# gmatrix.net
KiCad netlist of a schematic drawn in EAGLE
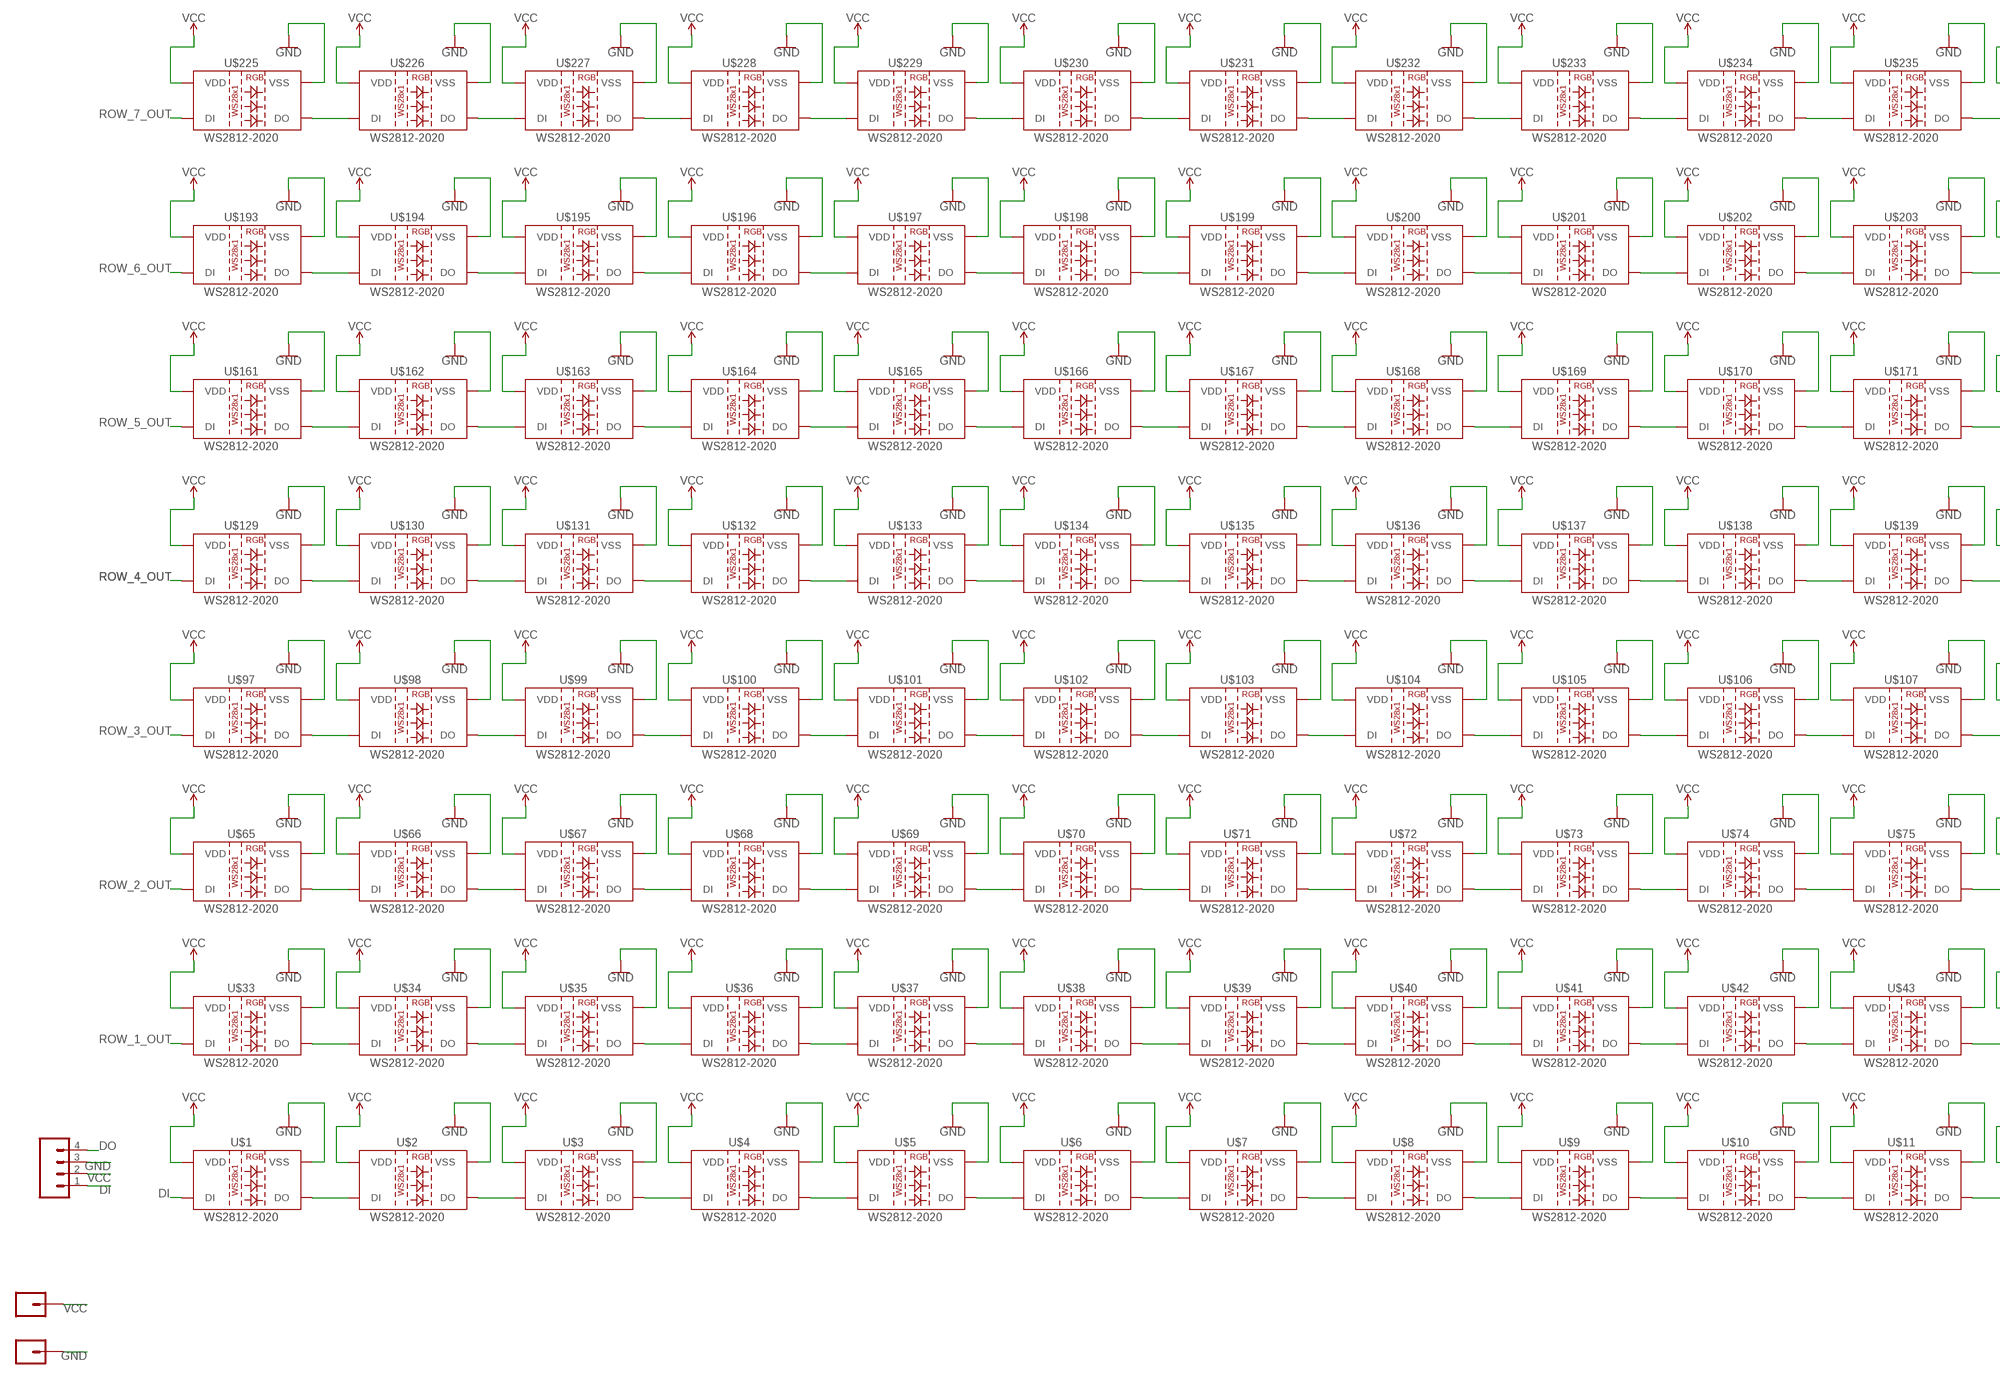
[diagram p0: schematic, sheet 1, part 1 of 3]
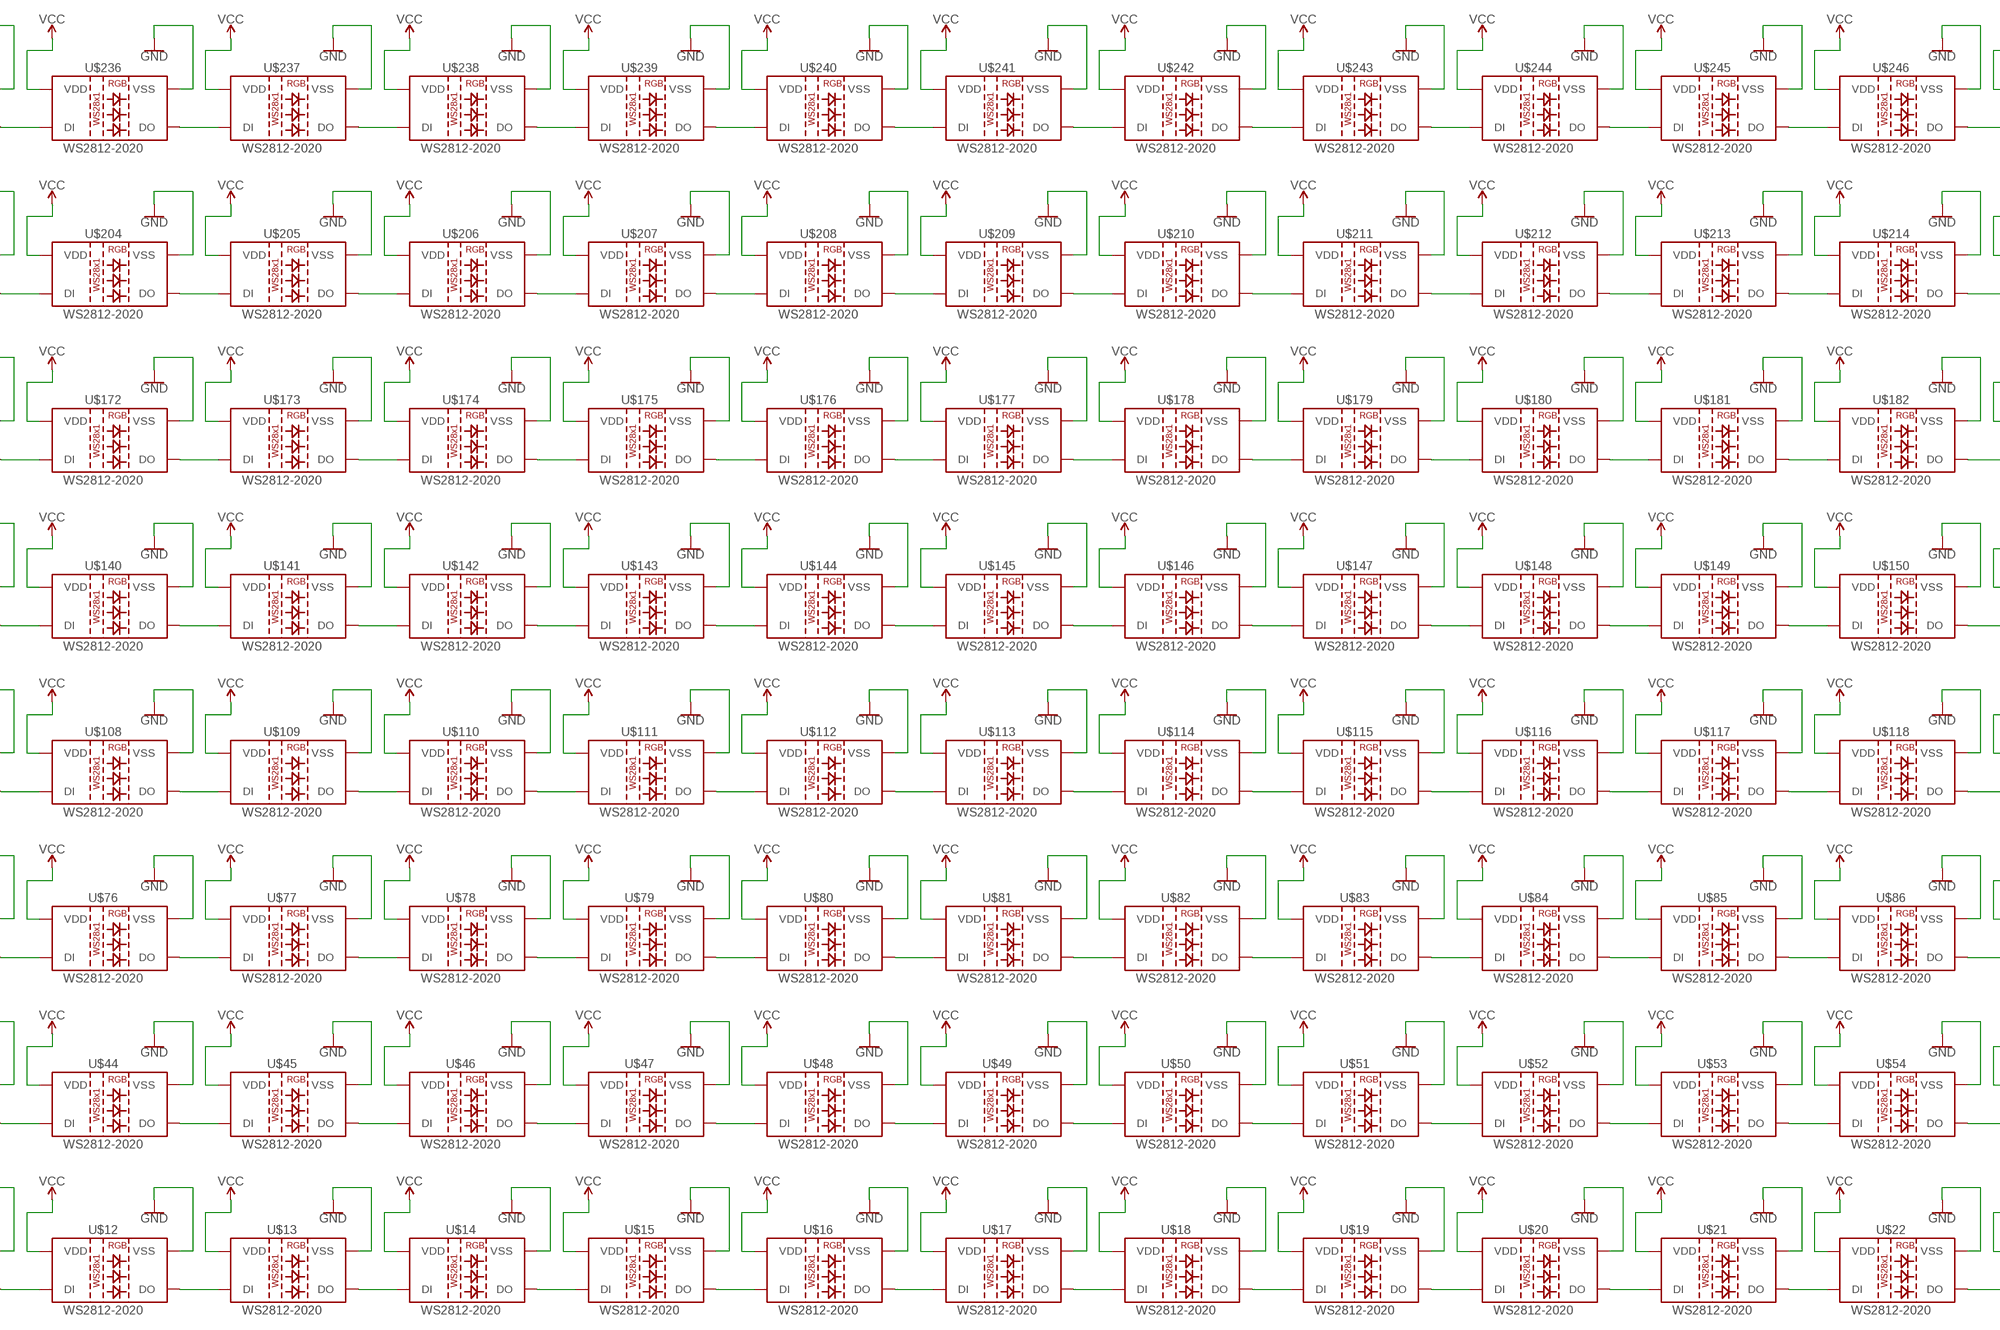
[diagram p1: schematic, sheet 1, part 2 of 3]
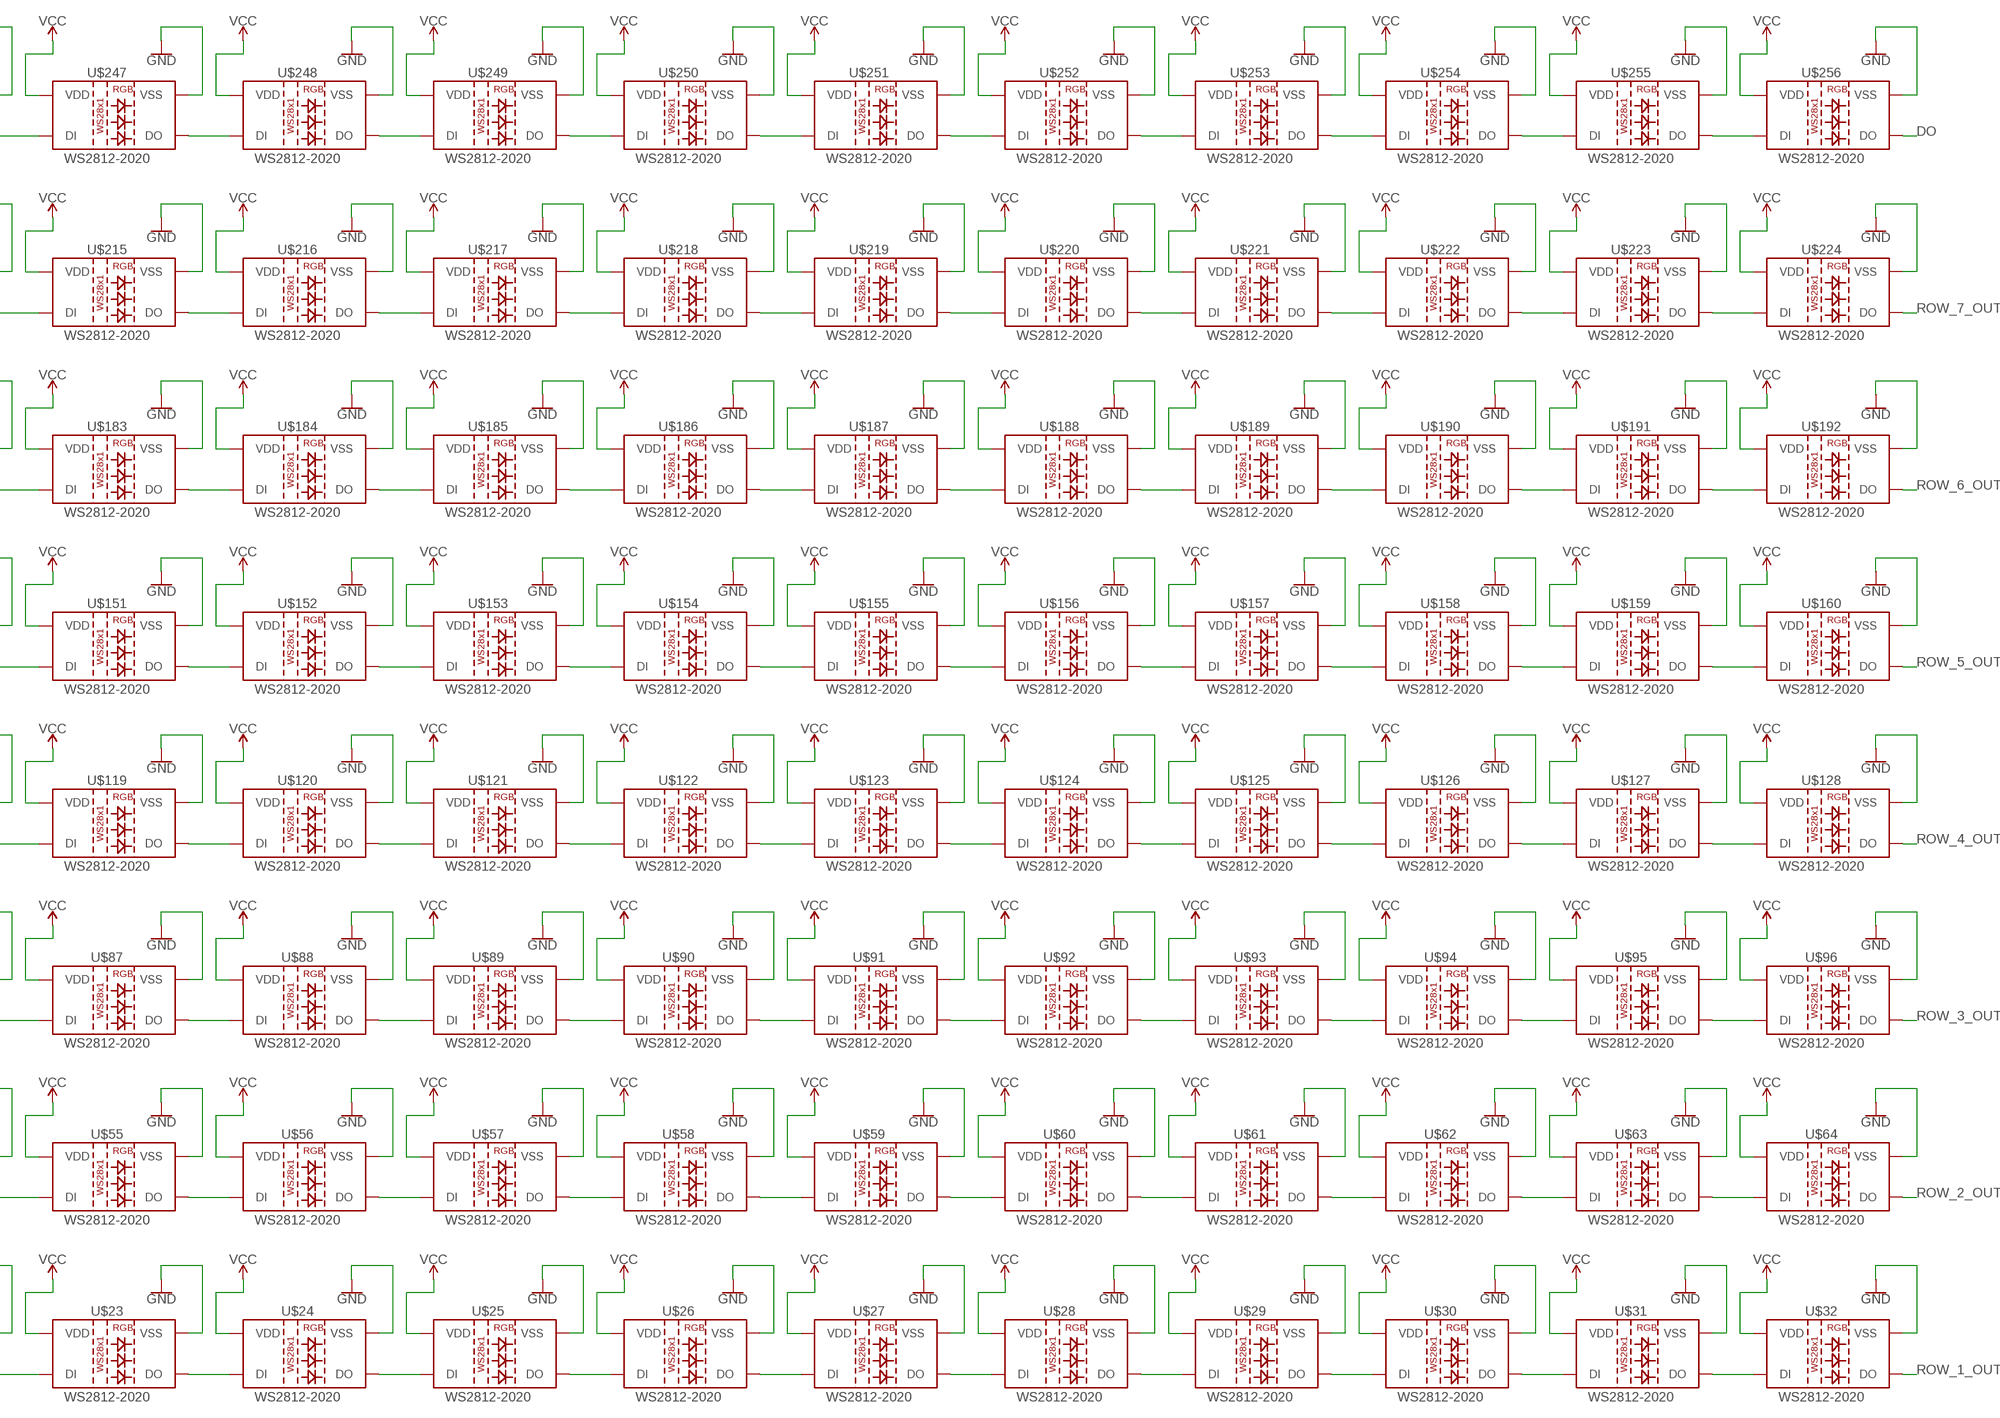
[diagram p2: schematic, sheet 1, part 3 of 3]

(export (version "E")
  (design (tool "Eeschema 10.0.6"))
  (components
    (comp (ref "J1")
      (value "CONN_041X04_NO_SILK")
      (footprint "eagle-import:1X04_NO_SILK")
      (libsource (lib "eagle-import") (part "CONN_041X04_NO_SILK"))
    )
    (comp (ref "J2")
      (value "CONN_01PTH_NO_SILK_KIT")
      (footprint "eagle-import:1X01NS_KIT")
      (libsource (lib "eagle-import") (part "CONN_01PTH_NO_SILK_KIT"))
    )
    (comp (ref "J3")
      (value "CONN_01PTH_NO_SILK_KIT")
      (footprint "eagle-import:1X01NS_KIT")
      (libsource (lib "eagle-import") (part "CONN_01PTH_NO_SILK_KIT"))
    )
    (comp (ref "U$1")
      (value "WS2812-2020")
      (footprint "eagle-import:WS2812-2020")
      (libsource (lib "eagle-import") (part "WS2812-2020"))
    )
    (comp (ref "U$2")
      (value "WS2812-2020")
      (footprint "eagle-import:WS2812-2020")
      (libsource (lib "eagle-import") (part "WS2812-2020"))
    )
    (comp (ref "U$3")
      (value "WS2812-2020")
      (footprint "eagle-import:WS2812-2020")
      (libsource (lib "eagle-import") (part "WS2812-2020"))
    )
    (comp (ref "U$4")
      (value "WS2812-2020")
      (footprint "eagle-import:WS2812-2020")
      (libsource (lib "eagle-import") (part "WS2812-2020"))
    )
    (comp (ref "U$5")
      (value "WS2812-2020")
      (footprint "eagle-import:WS2812-2020")
      (libsource (lib "eagle-import") (part "WS2812-2020"))
    )
    (comp (ref "U$6")
      (value "WS2812-2020")
      (footprint "eagle-import:WS2812-2020")
      (libsource (lib "eagle-import") (part "WS2812-2020"))
    )
    (comp (ref "U$7")
      (value "WS2812-2020")
      (footprint "eagle-import:WS2812-2020")
      (libsource (lib "eagle-import") (part "WS2812-2020"))
    )
    (comp (ref "U$8")
      (value "WS2812-2020")
      (footprint "eagle-import:WS2812-2020")
      (libsource (lib "eagle-import") (part "WS2812-2020"))
    )
    (comp (ref "U$9")
      (value "WS2812-2020")
      (footprint "eagle-import:WS2812-2020")
      (libsource (lib "eagle-import") (part "WS2812-2020"))
    )
    (comp (ref "U$10")
      (value "WS2812-2020")
      (footprint "eagle-import:WS2812-2020")
      (libsource (lib "eagle-import") (part "WS2812-2020"))
    )
    (comp (ref "U$11")
      (value "WS2812-2020")
      (footprint "eagle-import:WS2812-2020")
      (libsource (lib "eagle-import") (part "WS2812-2020"))
    )
    (comp (ref "U$12")
      (value "WS2812-2020")
      (footprint "eagle-import:WS2812-2020")
      (libsource (lib "eagle-import") (part "WS2812-2020"))
    )
    (comp (ref "U$13")
      (value "WS2812-2020")
      (footprint "eagle-import:WS2812-2020")
      (libsource (lib "eagle-import") (part "WS2812-2020"))
    )
    (comp (ref "U$14")
      (value "WS2812-2020")
      (footprint "eagle-import:WS2812-2020")
      (libsource (lib "eagle-import") (part "WS2812-2020"))
    )
    (comp (ref "U$15")
      (value "WS2812-2020")
      (footprint "eagle-import:WS2812-2020")
      (libsource (lib "eagle-import") (part "WS2812-2020"))
    )
    (comp (ref "U$16")
      (value "WS2812-2020")
      (footprint "eagle-import:WS2812-2020")
      (libsource (lib "eagle-import") (part "WS2812-2020"))
    )
    (comp (ref "U$17")
      (value "WS2812-2020")
      (footprint "eagle-import:WS2812-2020")
      (libsource (lib "eagle-import") (part "WS2812-2020"))
    )
    (comp (ref "U$18")
      (value "WS2812-2020")
      (footprint "eagle-import:WS2812-2020")
      (libsource (lib "eagle-import") (part "WS2812-2020"))
    )
    (comp (ref "U$19")
      (value "WS2812-2020")
      (footprint "eagle-import:WS2812-2020")
      (libsource (lib "eagle-import") (part "WS2812-2020"))
    )
    (comp (ref "U$20")
      (value "WS2812-2020")
      (footprint "eagle-import:WS2812-2020")
      (libsource (lib "eagle-import") (part "WS2812-2020"))
    )
    (comp (ref "U$21")
      (value "WS2812-2020")
      (footprint "eagle-import:WS2812-2020")
      (libsource (lib "eagle-import") (part "WS2812-2020"))
    )
    (comp (ref "U$22")
      (value "WS2812-2020")
      (footprint "eagle-import:WS2812-2020")
      (libsource (lib "eagle-import") (part "WS2812-2020"))
    )
    (comp (ref "U$23")
      (value "WS2812-2020")
      (footprint "eagle-import:WS2812-2020")
      (libsource (lib "eagle-import") (part "WS2812-2020"))
    )
    (comp (ref "U$24")
      (value "WS2812-2020")
      (footprint "eagle-import:WS2812-2020")
      (libsource (lib "eagle-import") (part "WS2812-2020"))
    )
    (comp (ref "U$25")
      (value "WS2812-2020")
      (footprint "eagle-import:WS2812-2020")
      (libsource (lib "eagle-import") (part "WS2812-2020"))
    )
    (comp (ref "U$26")
      (value "WS2812-2020")
      (footprint "eagle-import:WS2812-2020")
      (libsource (lib "eagle-import") (part "WS2812-2020"))
    )
    (comp (ref "U$27")
      (value "WS2812-2020")
      (footprint "eagle-import:WS2812-2020")
      (libsource (lib "eagle-import") (part "WS2812-2020"))
    )
    (comp (ref "U$28")
      (value "WS2812-2020")
      (footprint "eagle-import:WS2812-2020")
      (libsource (lib "eagle-import") (part "WS2812-2020"))
    )
    (comp (ref "U$29")
      (value "WS2812-2020")
      (footprint "eagle-import:WS2812-2020")
      (libsource (lib "eagle-import") (part "WS2812-2020"))
    )
    (comp (ref "U$30")
      (value "WS2812-2020")
      (footprint "eagle-import:WS2812-2020")
      (libsource (lib "eagle-import") (part "WS2812-2020"))
    )
    (comp (ref "U$31")
      (value "WS2812-2020")
      (footprint "eagle-import:WS2812-2020")
      (libsource (lib "eagle-import") (part "WS2812-2020"))
    )
    (comp (ref "U$32")
      (value "WS2812-2020")
      (footprint "eagle-import:WS2812-2020")
      (libsource (lib "eagle-import") (part "WS2812-2020"))
    )
    (comp (ref "U$33")
      (value "WS2812-2020")
      (footprint "eagle-import:WS2812-2020")
      (libsource (lib "eagle-import") (part "WS2812-2020"))
    )
    (comp (ref "U$34")
      (value "WS2812-2020")
      (footprint "eagle-import:WS2812-2020")
      (libsource (lib "eagle-import") (part "WS2812-2020"))
    )
    (comp (ref "U$35")
      (value "WS2812-2020")
      (footprint "eagle-import:WS2812-2020")
      (libsource (lib "eagle-import") (part "WS2812-2020"))
    )
    (comp (ref "U$36")
      (value "WS2812-2020")
      (footprint "eagle-import:WS2812-2020")
      (libsource (lib "eagle-import") (part "WS2812-2020"))
    )
    (comp (ref "U$37")
      (value "WS2812-2020")
      (footprint "eagle-import:WS2812-2020")
      (libsource (lib "eagle-import") (part "WS2812-2020"))
    )
    (comp (ref "U$38")
      (value "WS2812-2020")
      (footprint "eagle-import:WS2812-2020")
      (libsource (lib "eagle-import") (part "WS2812-2020"))
    )
    (comp (ref "U$39")
      (value "WS2812-2020")
      (footprint "eagle-import:WS2812-2020")
      (libsource (lib "eagle-import") (part "WS2812-2020"))
    )
    (comp (ref "U$40")
      (value "WS2812-2020")
      (footprint "eagle-import:WS2812-2020")
      (libsource (lib "eagle-import") (part "WS2812-2020"))
    )
    (comp (ref "U$41")
      (value "WS2812-2020")
      (footprint "eagle-import:WS2812-2020")
      (libsource (lib "eagle-import") (part "WS2812-2020"))
    )
    (comp (ref "U$42")
      (value "WS2812-2020")
      (footprint "eagle-import:WS2812-2020")
      (libsource (lib "eagle-import") (part "WS2812-2020"))
    )
    (comp (ref "U$43")
      (value "WS2812-2020")
      (footprint "eagle-import:WS2812-2020")
      (libsource (lib "eagle-import") (part "WS2812-2020"))
    )
    (comp (ref "U$44")
      (value "WS2812-2020")
      (footprint "eagle-import:WS2812-2020")
      (libsource (lib "eagle-import") (part "WS2812-2020"))
    )
    (comp (ref "U$45")
      (value "WS2812-2020")
      (footprint "eagle-import:WS2812-2020")
      (libsource (lib "eagle-import") (part "WS2812-2020"))
    )
    (comp (ref "U$46")
      (value "WS2812-2020")
      (footprint "eagle-import:WS2812-2020")
      (libsource (lib "eagle-import") (part "WS2812-2020"))
    )
    (comp (ref "U$47")
      (value "WS2812-2020")
      (footprint "eagle-import:WS2812-2020")
      (libsource (lib "eagle-import") (part "WS2812-2020"))
    )
    (comp (ref "U$48")
      (value "WS2812-2020")
      (footprint "eagle-import:WS2812-2020")
      (libsource (lib "eagle-import") (part "WS2812-2020"))
    )
    (comp (ref "U$49")
      (value "WS2812-2020")
      (footprint "eagle-import:WS2812-2020")
      (libsource (lib "eagle-import") (part "WS2812-2020"))
    )
    (comp (ref "U$50")
      (value "WS2812-2020")
      (footprint "eagle-import:WS2812-2020")
      (libsource (lib "eagle-import") (part "WS2812-2020"))
    )
    (comp (ref "U$51")
      (value "WS2812-2020")
      (footprint "eagle-import:WS2812-2020")
      (libsource (lib "eagle-import") (part "WS2812-2020"))
    )
    (comp (ref "U$52")
      (value "WS2812-2020")
      (footprint "eagle-import:WS2812-2020")
      (libsource (lib "eagle-import") (part "WS2812-2020"))
    )
    (comp (ref "U$53")
      (value "WS2812-2020")
      (footprint "eagle-import:WS2812-2020")
      (libsource (lib "eagle-import") (part "WS2812-2020"))
    )
    (comp (ref "U$54")
      (value "WS2812-2020")
      (footprint "eagle-import:WS2812-2020")
      (libsource (lib "eagle-import") (part "WS2812-2020"))
    )
    (comp (ref "U$55")
      (value "WS2812-2020")
      (footprint "eagle-import:WS2812-2020")
      (libsource (lib "eagle-import") (part "WS2812-2020"))
    )
    (comp (ref "U$56")
      (value "WS2812-2020")
      (footprint "eagle-import:WS2812-2020")
      (libsource (lib "eagle-import") (part "WS2812-2020"))
    )
    (comp (ref "U$57")
      (value "WS2812-2020")
      (footprint "eagle-import:WS2812-2020")
      (libsource (lib "eagle-import") (part "WS2812-2020"))
    )
    (comp (ref "U$58")
      (value "WS2812-2020")
      (footprint "eagle-import:WS2812-2020")
      (libsource (lib "eagle-import") (part "WS2812-2020"))
    )
    (comp (ref "U$59")
      (value "WS2812-2020")
      (footprint "eagle-import:WS2812-2020")
      (libsource (lib "eagle-import") (part "WS2812-2020"))
    )
    (comp (ref "U$60")
      (value "WS2812-2020")
      (footprint "eagle-import:WS2812-2020")
      (libsource (lib "eagle-import") (part "WS2812-2020"))
    )
    (comp (ref "U$61")
      (value "WS2812-2020")
      (footprint "eagle-import:WS2812-2020")
      (libsource (lib "eagle-import") (part "WS2812-2020"))
    )
    (comp (ref "U$62")
      (value "WS2812-2020")
      (footprint "eagle-import:WS2812-2020")
      (libsource (lib "eagle-import") (part "WS2812-2020"))
    )
    (comp (ref "U$63")
      (value "WS2812-2020")
      (footprint "eagle-import:WS2812-2020")
      (libsource (lib "eagle-import") (part "WS2812-2020"))
    )
    (comp (ref "U$64")
      (value "WS2812-2020")
      (footprint "eagle-import:WS2812-2020")
      (libsource (lib "eagle-import") (part "WS2812-2020"))
    )
    (comp (ref "U$65")
      (value "WS2812-2020")
      (footprint "eagle-import:WS2812-2020")
      (libsource (lib "eagle-import") (part "WS2812-2020"))
    )
    (comp (ref "U$66")
      (value "WS2812-2020")
      (footprint "eagle-import:WS2812-2020")
      (libsource (lib "eagle-import") (part "WS2812-2020"))
    )
    (comp (ref "U$67")
      (value "WS2812-2020")
      (footprint "eagle-import:WS2812-2020")
      (libsource (lib "eagle-import") (part "WS2812-2020"))
    )
    (comp (ref "U$68")
      (value "WS2812-2020")
      (footprint "eagle-import:WS2812-2020")
      (libsource (lib "eagle-import") (part "WS2812-2020"))
    )
    (comp (ref "U$69")
      (value "WS2812-2020")
      (footprint "eagle-import:WS2812-2020")
      (libsource (lib "eagle-import") (part "WS2812-2020"))
    )
    (comp (ref "U$70")
      (value "WS2812-2020")
      (footprint "eagle-import:WS2812-2020")
      (libsource (lib "eagle-import") (part "WS2812-2020"))
    )
    (comp (ref "U$71")
      (value "WS2812-2020")
      (footprint "eagle-import:WS2812-2020")
      (libsource (lib "eagle-import") (part "WS2812-2020"))
    )
    (comp (ref "U$72")
      (value "WS2812-2020")
      (footprint "eagle-import:WS2812-2020")
      (libsource (lib "eagle-import") (part "WS2812-2020"))
    )
    (comp (ref "U$73")
      (value "WS2812-2020")
      (footprint "eagle-import:WS2812-2020")
      (libsource (lib "eagle-import") (part "WS2812-2020"))
    )
    (comp (ref "U$74")
      (value "WS2812-2020")
      (footprint "eagle-import:WS2812-2020")
      (libsource (lib "eagle-import") (part "WS2812-2020"))
    )
    (comp (ref "U$75")
      (value "WS2812-2020")
      (footprint "eagle-import:WS2812-2020")
      (libsource (lib "eagle-import") (part "WS2812-2020"))
    )
    (comp (ref "U$76")
      (value "WS2812-2020")
      (footprint "eagle-import:WS2812-2020")
      (libsource (lib "eagle-import") (part "WS2812-2020"))
    )
    (comp (ref "U$77")
      (value "WS2812-2020")
      (footprint "eagle-import:WS2812-2020")
      (libsource (lib "eagle-import") (part "WS2812-2020"))
    )
    (comp (ref "U$78")
      (value "WS2812-2020")
      (footprint "eagle-import:WS2812-2020")
      (libsource (lib "eagle-import") (part "WS2812-2020"))
    )
    (comp (ref "U$79")
      (value "WS2812-2020")
      (footprint "eagle-import:WS2812-2020")
      (libsource (lib "eagle-import") (part "WS2812-2020"))
    )
    (comp (ref "U$80")
      (value "WS2812-2020")
      (footprint "eagle-import:WS2812-2020")
      (libsource (lib "eagle-import") (part "WS2812-2020"))
    )
    (comp (ref "U$81")
      (value "WS2812-2020")
      (footprint "eagle-import:WS2812-2020")
      (libsource (lib "eagle-import") (part "WS2812-2020"))
    )
    (comp (ref "U$82")
      (value "WS2812-2020")
      (footprint "eagle-import:WS2812-2020")
      (libsource (lib "eagle-import") (part "WS2812-2020"))
    )
    (comp (ref "U$83")
      (value "WS2812-2020")
      (footprint "eagle-import:WS2812-2020")
      (libsource (lib "eagle-import") (part "WS2812-2020"))
    )
    (comp (ref "U$84")
      (value "WS2812-2020")
      (footprint "eagle-import:WS2812-2020")
      (libsource (lib "eagle-import") (part "WS2812-2020"))
    )
    (comp (ref "U$85")
      (value "WS2812-2020")
      (footprint "eagle-import:WS2812-2020")
      (libsource (lib "eagle-import") (part "WS2812-2020"))
    )
    (comp (ref "U$86")
      (value "WS2812-2020")
      (footprint "eagle-import:WS2812-2020")
      (libsource (lib "eagle-import") (part "WS2812-2020"))
    )
    (comp (ref "U$87")
      (value "WS2812-2020")
      (footprint "eagle-import:WS2812-2020")
      (libsource (lib "eagle-import") (part "WS2812-2020"))
    )
    (comp (ref "U$88")
      (value "WS2812-2020")
      (footprint "eagle-import:WS2812-2020")
      (libsource (lib "eagle-import") (part "WS2812-2020"))
    )
    (comp (ref "U$89")
      (value "WS2812-2020")
      (footprint "eagle-import:WS2812-2020")
      (libsource (lib "eagle-import") (part "WS2812-2020"))
    )
    (comp (ref "U$90")
      (value "WS2812-2020")
      (footprint "eagle-import:WS2812-2020")
      (libsource (lib "eagle-import") (part "WS2812-2020"))
    )
    (comp (ref "U$91")
      (value "WS2812-2020")
      (footprint "eagle-import:WS2812-2020")
      (libsource (lib "eagle-import") (part "WS2812-2020"))
    )
    (comp (ref "U$92")
      (value "WS2812-2020")
      (footprint "eagle-import:WS2812-2020")
      (libsource (lib "eagle-import") (part "WS2812-2020"))
    )
    (comp (ref "U$93")
      (value "WS2812-2020")
      (footprint "eagle-import:WS2812-2020")
      (libsource (lib "eagle-import") (part "WS2812-2020"))
    )
    (comp (ref "U$94")
      (value "WS2812-2020")
      (footprint "eagle-import:WS2812-2020")
      (libsource (lib "eagle-import") (part "WS2812-2020"))
    )
    (comp (ref "U$95")
      (value "WS2812-2020")
      (footprint "eagle-import:WS2812-2020")
      (libsource (lib "eagle-import") (part "WS2812-2020"))
    )
    (comp (ref "U$96")
      (value "WS2812-2020")
      (footprint "eagle-import:WS2812-2020")
      (libsource (lib "eagle-import") (part "WS2812-2020"))
    )
    (comp (ref "U$97")
      (value "WS2812-2020")
      (footprint "eagle-import:WS2812-2020")
      (libsource (lib "eagle-import") (part "WS2812-2020"))
    )
    (comp (ref "U$98")
      (value "WS2812-2020")
      (footprint "eagle-import:WS2812-2020")
      (libsource (lib "eagle-import") (part "WS2812-2020"))
    )
    (comp (ref "U$99")
      (value "WS2812-2020")
      (footprint "eagle-import:WS2812-2020")
      (libsource (lib "eagle-import") (part "WS2812-2020"))
    )
    (comp (ref "U$100")
      (value "WS2812-2020")
      (footprint "eagle-import:WS2812-2020")
      (libsource (lib "eagle-import") (part "WS2812-2020"))
    )
    (comp (ref "U$101")
      (value "WS2812-2020")
      (footprint "eagle-import:WS2812-2020")
      (libsource (lib "eagle-import") (part "WS2812-2020"))
    )
    (comp (ref "U$102")
      (value "WS2812-2020")
      (footprint "eagle-import:WS2812-2020")
      (libsource (lib "eagle-import") (part "WS2812-2020"))
    )
    (comp (ref "U$103")
      (value "WS2812-2020")
      (footprint "eagle-import:WS2812-2020")
      (libsource (lib "eagle-import") (part "WS2812-2020"))
    )
    (comp (ref "U$104")
      (value "WS2812-2020")
      (footprint "eagle-import:WS2812-2020")
      (libsource (lib "eagle-import") (part "WS2812-2020"))
    )
    (comp (ref "U$105")
      (value "WS2812-2020")
      (footprint "eagle-import:WS2812-2020")
      (libsource (lib "eagle-import") (part "WS2812-2020"))
    )
    (comp (ref "U$106")
      (value "WS2812-2020")
      (footprint "eagle-import:WS2812-2020")
      (libsource (lib "eagle-import") (part "WS2812-2020"))
    )
    (comp (ref "U$107")
      (value "WS2812-2020")
      (footprint "eagle-import:WS2812-2020")
      (libsource (lib "eagle-import") (part "WS2812-2020"))
    )
    (comp (ref "U$108")
      (value "WS2812-2020")
      (footprint "eagle-import:WS2812-2020")
      (libsource (lib "eagle-import") (part "WS2812-2020"))
    )
    (comp (ref "U$109")
      (value "WS2812-2020")
      (footprint "eagle-import:WS2812-2020")
      (libsource (lib "eagle-import") (part "WS2812-2020"))
    )
    (comp (ref "U$110")
      (value "WS2812-2020")
      (footprint "eagle-import:WS2812-2020")
      (libsource (lib "eagle-import") (part "WS2812-2020"))
    )
    (comp (ref "U$111")
      (value "WS2812-2020")
      (footprint "eagle-import:WS2812-2020")
      (libsource (lib "eagle-import") (part "WS2812-2020"))
    )
    (comp (ref "U$112")
      (value "WS2812-2020")
      (footprint "eagle-import:WS2812-2020")
      (libsource (lib "eagle-import") (part "WS2812-2020"))
    )
    (comp (ref "U$113")
      (value "WS2812-2020")
      (footprint "eagle-import:WS2812-2020")
      (libsource (lib "eagle-import") (part "WS2812-2020"))
    )
    (comp (ref "U$114")
      (value "WS2812-2020")
      (footprint "eagle-import:WS2812-2020")
      (libsource (lib "eagle-import") (part "WS2812-2020"))
    )
    (comp (ref "U$115")
      (value "WS2812-2020")
      (footprint "eagle-import:WS2812-2020")
      (libsource (lib "eagle-import") (part "WS2812-2020"))
    )
    (comp (ref "U$116")
      (value "WS2812-2020")
      (footprint "eagle-import:WS2812-2020")
      (libsource (lib "eagle-import") (part "WS2812-2020"))
    )
    (comp (ref "U$117")
      (value "WS2812-2020")
      (footprint "eagle-import:WS2812-2020")
      (libsource (lib "eagle-import") (part "WS2812-2020"))
    )
    (comp (ref "U$118")
      (value "WS2812-2020")
      (footprint "eagle-import:WS2812-2020")
      (libsource (lib "eagle-import") (part "WS2812-2020"))
    )
    (comp (ref "U$119")
      (value "WS2812-2020")
      (footprint "eagle-import:WS2812-2020")
      (libsource (lib "eagle-import") (part "WS2812-2020"))
    )
    (comp (ref "U$120")
      (value "WS2812-2020")
      (footprint "eagle-import:WS2812-2020")
      (libsource (lib "eagle-import") (part "WS2812-2020"))
    )
    (comp (ref "U$121")
      (value "WS2812-2020")
      (footprint "eagle-import:WS2812-2020")
      (libsource (lib "eagle-import") (part "WS2812-2020"))
    )
    (comp (ref "U$122")
      (value "WS2812-2020")
      (footprint "eagle-import:WS2812-2020")
      (libsource (lib "eagle-import") (part "WS2812-2020"))
    )
    (comp (ref "U$123")
      (value "WS2812-2020")
      (footprint "eagle-import:WS2812-2020")
      (libsource (lib "eagle-import") (part "WS2812-2020"))
    )
    (comp (ref "U$124")
      (value "WS2812-2020")
      (footprint "eagle-import:WS2812-2020")
      (libsource (lib "eagle-import") (part "WS2812-2020"))
    )
    (comp (ref "U$125")
      (value "WS2812-2020")
      (footprint "eagle-import:WS2812-2020")
      (libsource (lib "eagle-import") (part "WS2812-2020"))
    )
    (comp (ref "U$126")
      (value "WS2812-2020")
      (footprint "eagle-import:WS2812-2020")
      (libsource (lib "eagle-import") (part "WS2812-2020"))
    )
    (comp (ref "U$127")
      (value "WS2812-2020")
      (footprint "eagle-import:WS2812-2020")
      (libsource (lib "eagle-import") (part "WS2812-2020"))
    )
    (comp (ref "U$128")
      (value "WS2812-2020")
      (footprint "eagle-import:WS2812-2020")
      (libsource (lib "eagle-import") (part "WS2812-2020"))
    )
    (comp (ref "U$129")
      (value "WS2812-2020")
      (footprint "eagle-import:WS2812-2020")
      (libsource (lib "eagle-import") (part "WS2812-2020"))
    )
    (comp (ref "U$130")
      (value "WS2812-2020")
      (footprint "eagle-import:WS2812-2020")
      (libsource (lib "eagle-import") (part "WS2812-2020"))
    )
    (comp (ref "U$131")
      (value "WS2812-2020")
      (footprint "eagle-import:WS2812-2020")
      (libsource (lib "eagle-import") (part "WS2812-2020"))
    )
    (comp (ref "U$132")
      (value "WS2812-2020")
      (footprint "eagle-import:WS2812-2020")
      (libsource (lib "eagle-import") (part "WS2812-2020"))
    )
    (comp (ref "U$133")
      (value "WS2812-2020")
      (footprint "eagle-import:WS2812-2020")
      (libsource (lib "eagle-import") (part "WS2812-2020"))
    )
    (comp (ref "U$134")
      (value "WS2812-2020")
      (footprint "eagle-import:WS2812-2020")
      (libsource (lib "eagle-import") (part "WS2812-2020"))
    )
    (comp (ref "U$135")
      (value "WS2812-2020")
      (footprint "eagle-import:WS2812-2020")
      (libsource (lib "eagle-import") (part "WS2812-2020"))
    )
    (comp (ref "U$136")
      (value "WS2812-2020")
      (footprint "eagle-import:WS2812-2020")
      (libsource (lib "eagle-import") (part "WS2812-2020"))
    )
    (comp (ref "U$137")
      (value "WS2812-2020")
      (footprint "eagle-import:WS2812-2020")
      (libsource (lib "eagle-import") (part "WS2812-2020"))
    )
    (comp (ref "U$138")
      (value "WS2812-2020")
      (footprint "eagle-import:WS2812-2020")
      (libsource (lib "eagle-import") (part "WS2812-2020"))
    )
    (comp (ref "U$139")
      (value "WS2812-2020")
      (footprint "eagle-import:WS2812-2020")
      (libsource (lib "eagle-import") (part "WS2812-2020"))
    )
    (comp (ref "U$140")
      (value "WS2812-2020")
      (footprint "eagle-import:WS2812-2020")
      (libsource (lib "eagle-import") (part "WS2812-2020"))
    )
    (comp (ref "U$141")
      (value "WS2812-2020")
      (footprint "eagle-import:WS2812-2020")
      (libsource (lib "eagle-import") (part "WS2812-2020"))
    )
    (comp (ref "U$142")
      (value "WS2812-2020")
      (footprint "eagle-import:WS2812-2020")
      (libsource (lib "eagle-import") (part "WS2812-2020"))
    )
    (comp (ref "U$143")
      (value "WS2812-2020")
      (footprint "eagle-import:WS2812-2020")
      (libsource (lib "eagle-import") (part "WS2812-2020"))
    )
    (comp (ref "U$144")
      (value "WS2812-2020")
      (footprint "eagle-import:WS2812-2020")
      (libsource (lib "eagle-import") (part "WS2812-2020"))
    )
    (comp (ref "U$145")
      (value "WS2812-2020")
      (footprint "eagle-import:WS2812-2020")
      (libsource (lib "eagle-import") (part "WS2812-2020"))
    )
    (comp (ref "U$146")
      (value "WS2812-2020")
      (footprint "eagle-import:WS2812-2020")
      (libsource (lib "eagle-import") (part "WS2812-2020"))
    )
    (comp (ref "U$147")
      (value "WS2812-2020")
      (footprint "eagle-import:WS2812-2020")
      (libsource (lib "eagle-import") (part "WS2812-2020"))
    )
    (comp (ref "U$148")
      (value "WS2812-2020")
      (footprint "eagle-import:WS2812-2020")
      (libsource (lib "eagle-import") (part "WS2812-2020"))
    )
    (comp (ref "U$149")
      (value "WS2812-2020")
      (footprint "eagle-import:WS2812-2020")
      (libsource (lib "eagle-import") (part "WS2812-2020"))
    )
    (comp (ref "U$150")
      (value "WS2812-2020")
      (footprint "eagle-import:WS2812-2020")
      (libsource (lib "eagle-import") (part "WS2812-2020"))
    )
    (comp (ref "U$151")
      (value "WS2812-2020")
      (footprint "eagle-import:WS2812-2020")
      (libsource (lib "eagle-import") (part "WS2812-2020"))
    )
    (comp (ref "U$152")
      (value "WS2812-2020")
      (footprint "eagle-import:WS2812-2020")
      (libsource (lib "eagle-import") (part "WS2812-2020"))
    )
    (comp (ref "U$153")
      (value "WS2812-2020")
      (footprint "eagle-import:WS2812-2020")
      (libsource (lib "eagle-import") (part "WS2812-2020"))
    )
    (comp (ref "U$154")
      (value "WS2812-2020")
      (footprint "eagle-import:WS2812-2020")
      (libsource (lib "eagle-import") (part "WS2812-2020"))
    )
    (comp (ref "U$155")
      (value "WS2812-2020")
      (footprint "eagle-import:WS2812-2020")
      (libsource (lib "eagle-import") (part "WS2812-2020"))
    )
    (comp (ref "U$156")
      (value "WS2812-2020")
      (footprint "eagle-import:WS2812-2020")
      (libsource (lib "eagle-import") (part "WS2812-2020"))
    )
    (comp (ref "U$157")
      (value "WS2812-2020")
      (footprint "eagle-import:WS2812-2020")
      (libsource (lib "eagle-import") (part "WS2812-2020"))
    )
    (comp (ref "U$158")
      (value "WS2812-2020")
      (footprint "eagle-import:WS2812-2020")
      (libsource (lib "eagle-import") (part "WS2812-2020"))
    )
    (comp (ref "U$159")
      (value "WS2812-2020")
      (footprint "eagle-import:WS2812-2020")
      (libsource (lib "eagle-import") (part "WS2812-2020"))
    )
    (comp (ref "U$160")
      (value "WS2812-2020")
      (footprint "eagle-import:WS2812-2020")
      (libsource (lib "eagle-import") (part "WS2812-2020"))
    )
    (comp (ref "U$161")
      (value "WS2812-2020")
      (footprint "eagle-import:WS2812-2020")
      (libsource (lib "eagle-import") (part "WS2812-2020"))
    )
    (comp (ref "U$162")
      (value "WS2812-2020")
      (footprint "eagle-import:WS2812-2020")
      (libsource (lib "eagle-import") (part "WS2812-2020"))
    )
    (comp (ref "U$163")
      (value "WS2812-2020")
      (footprint "eagle-import:WS2812-2020")
      (libsource (lib "eagle-import") (part "WS2812-2020"))
    )
    (comp (ref "U$164")
      (value "WS2812-2020")
      (footprint "eagle-import:WS2812-2020")
      (libsource (lib "eagle-import") (part "WS2812-2020"))
    )
    (comp (ref "U$165")
      (value "WS2812-2020")
      (footprint "eagle-import:WS2812-2020")
      (libsource (lib "eagle-import") (part "WS2812-2020"))
    )
    (comp (ref "U$166")
      (value "WS2812-2020")
      (footprint "eagle-import:WS2812-2020")
      (libsource (lib "eagle-import") (part "WS2812-2020"))
    )
    (comp (ref "U$167")
      (value "WS2812-2020")
      (footprint "eagle-import:WS2812-2020")
      (libsource (lib "eagle-import") (part "WS2812-2020"))
    )
    (comp (ref "U$168")
      (value "WS2812-2020")
      (footprint "eagle-import:WS2812-2020")
      (libsource (lib "eagle-import") (part "WS2812-2020"))
    )
    (comp (ref "U$169")
      (value "WS2812-2020")
      (footprint "eagle-import:WS2812-2020")
      (libsource (lib "eagle-import") (part "WS2812-2020"))
    )
    (comp (ref "U$170")
      (value "WS2812-2020")
      (footprint "eagle-import:WS2812-2020")
      (libsource (lib "eagle-import") (part "WS2812-2020"))
    )
    (comp (ref "U$171")
      (value "WS2812-2020")
      (footprint "eagle-import:WS2812-2020")
      (libsource (lib "eagle-import") (part "WS2812-2020"))
    )
    (comp (ref "U$172")
      (value "WS2812-2020")
      (footprint "eagle-import:WS2812-2020")
      (libsource (lib "eagle-import") (part "WS2812-2020"))
    )
    (comp (ref "U$173")
      (value "WS2812-2020")
      (footprint "eagle-import:WS2812-2020")
      (libsource (lib "eagle-import") (part "WS2812-2020"))
    )
    (comp (ref "U$174")
      (value "WS2812-2020")
      (footprint "eagle-import:WS2812-2020")
      (libsource (lib "eagle-import") (part "WS2812-2020"))
    )
    (comp (ref "U$175")
      (value "WS2812-2020")
      (footprint "eagle-import:WS2812-2020")
      (libsource (lib "eagle-import") (part "WS2812-2020"))
    )
    (comp (ref "U$176")
      (value "WS2812-2020")
      (footprint "eagle-import:WS2812-2020")
      (libsource (lib "eagle-import") (part "WS2812-2020"))
    )
    (comp (ref "U$177")
      (value "WS2812-2020")
      (footprint "eagle-import:WS2812-2020")
      (libsource (lib "eagle-import") (part "WS2812-2020"))
    )
    (comp (ref "U$178")
      (value "WS2812-2020")
      (footprint "eagle-import:WS2812-2020")
      (libsource (lib "eagle-import") (part "WS2812-2020"))
    )
    (comp (ref "U$179")
      (value "WS2812-2020")
      (footprint "eagle-import:WS2812-2020")
      (libsource (lib "eagle-import") (part "WS2812-2020"))
    )
    (comp (ref "U$180")
      (value "WS2812-2020")
      (footprint "eagle-import:WS2812-2020")
      (libsource (lib "eagle-import") (part "WS2812-2020"))
    )
    (comp (ref "U$181")
      (value "WS2812-2020")
      (footprint "eagle-import:WS2812-2020")
      (libsource (lib "eagle-import") (part "WS2812-2020"))
    )
    (comp (ref "U$182")
      (value "WS2812-2020")
      (footprint "eagle-import:WS2812-2020")
      (libsource (lib "eagle-import") (part "WS2812-2020"))
    )
    (comp (ref "U$183")
      (value "WS2812-2020")
      (footprint "eagle-import:WS2812-2020")
      (libsource (lib "eagle-import") (part "WS2812-2020"))
    )
    (comp (ref "U$184")
      (value "WS2812-2020")
      (footprint "eagle-import:WS2812-2020")
      (libsource (lib "eagle-import") (part "WS2812-2020"))
    )
    (comp (ref "U$185")
      (value "WS2812-2020")
      (footprint "eagle-import:WS2812-2020")
      (libsource (lib "eagle-import") (part "WS2812-2020"))
    )
    (comp (ref "U$186")
      (value "WS2812-2020")
      (footprint "eagle-import:WS2812-2020")
      (libsource (lib "eagle-import") (part "WS2812-2020"))
    )
    (comp (ref "U$187")
      (value "WS2812-2020")
      (footprint "eagle-import:WS2812-2020")
      (libsource (lib "eagle-import") (part "WS2812-2020"))
    )
    (comp (ref "U$188")
      (value "WS2812-2020")
      (footprint "eagle-import:WS2812-2020")
      (libsource (lib "eagle-import") (part "WS2812-2020"))
    )
    (comp (ref "U$189")
      (value "WS2812-2020")
      (footprint "eagle-import:WS2812-2020")
      (libsource (lib "eagle-import") (part "WS2812-2020"))
    )
    (comp (ref "U$190")
      (value "WS2812-2020")
      (footprint "eagle-import:WS2812-2020")
      (libsource (lib "eagle-import") (part "WS2812-2020"))
    )
    (comp (ref "U$191")
      (value "WS2812-2020")
      (footprint "eagle-import:WS2812-2020")
      (libsource (lib "eagle-import") (part "WS2812-2020"))
    )
    (comp (ref "U$192")
      (value "WS2812-2020")
      (footprint "eagle-import:WS2812-2020")
      (libsource (lib "eagle-import") (part "WS2812-2020"))
    )
    (comp (ref "U$193")
      (value "WS2812-2020")
      (footprint "eagle-import:WS2812-2020")
      (libsource (lib "eagle-import") (part "WS2812-2020"))
    )
    (comp (ref "U$194")
      (value "WS2812-2020")
      (footprint "eagle-import:WS2812-2020")
      (libsource (lib "eagle-import") (part "WS2812-2020"))
    )
    (comp (ref "U$195")
      (value "WS2812-2020")
      (footprint "eagle-import:WS2812-2020")
      (libsource (lib "eagle-import") (part "WS2812-2020"))
    )
    (comp (ref "U$196")
      (value "WS2812-2020")
      (footprint "eagle-import:WS2812-2020")
      (libsource (lib "eagle-import") (part "WS2812-2020"))
    )
    (comp (ref "U$197")
      (value "WS2812-2020")
      (footprint "eagle-import:WS2812-2020")
      (libsource (lib "eagle-import") (part "WS2812-2020"))
    )
    (comp (ref "U$198")
      (value "WS2812-2020")
      (footprint "eagle-import:WS2812-2020")
      (libsource (lib "eagle-import") (part "WS2812-2020"))
    )
    (comp (ref "U$199")
      (value "WS2812-2020")
      (footprint "eagle-import:WS2812-2020")
      (libsource (lib "eagle-import") (part "WS2812-2020"))
    )
    (comp (ref "U$200")
      (value "WS2812-2020")
      (footprint "eagle-import:WS2812-2020")
      (libsource (lib "eagle-import") (part "WS2812-2020"))
    )
    (comp (ref "U$201")
      (value "WS2812-2020")
      (footprint "eagle-import:WS2812-2020")
      (libsource (lib "eagle-import") (part "WS2812-2020"))
    )
    (comp (ref "U$202")
      (value "WS2812-2020")
      (footprint "eagle-import:WS2812-2020")
      (libsource (lib "eagle-import") (part "WS2812-2020"))
    )
    (comp (ref "U$203")
      (value "WS2812-2020")
      (footprint "eagle-import:WS2812-2020")
      (libsource (lib "eagle-import") (part "WS2812-2020"))
    )
    (comp (ref "U$204")
      (value "WS2812-2020")
      (footprint "eagle-import:WS2812-2020")
      (libsource (lib "eagle-import") (part "WS2812-2020"))
    )
    (comp (ref "U$205")
      (value "WS2812-2020")
      (footprint "eagle-import:WS2812-2020")
      (libsource (lib "eagle-import") (part "WS2812-2020"))
    )
    (comp (ref "U$206")
      (value "WS2812-2020")
      (footprint "eagle-import:WS2812-2020")
      (libsource (lib "eagle-import") (part "WS2812-2020"))
    )
    (comp (ref "U$207")
      (value "WS2812-2020")
      (footprint "eagle-import:WS2812-2020")
      (libsource (lib "eagle-import") (part "WS2812-2020"))
    )
    (comp (ref "U$208")
      (value "WS2812-2020")
      (footprint "eagle-import:WS2812-2020")
      (libsource (lib "eagle-import") (part "WS2812-2020"))
    )
    (comp (ref "U$209")
      (value "WS2812-2020")
      (footprint "eagle-import:WS2812-2020")
      (libsource (lib "eagle-import") (part "WS2812-2020"))
    )
    (comp (ref "U$210")
      (value "WS2812-2020")
      (footprint "eagle-import:WS2812-2020")
      (libsource (lib "eagle-import") (part "WS2812-2020"))
    )
    (comp (ref "U$211")
      (value "WS2812-2020")
      (footprint "eagle-import:WS2812-2020")
      (libsource (lib "eagle-import") (part "WS2812-2020"))
    )
    (comp (ref "U$212")
      (value "WS2812-2020")
      (footprint "eagle-import:WS2812-2020")
      (libsource (lib "eagle-import") (part "WS2812-2020"))
    )
    (comp (ref "U$213")
      (value "WS2812-2020")
      (footprint "eagle-import:WS2812-2020")
      (libsource (lib "eagle-import") (part "WS2812-2020"))
    )
    (comp (ref "U$214")
      (value "WS2812-2020")
      (footprint "eagle-import:WS2812-2020")
      (libsource (lib "eagle-import") (part "WS2812-2020"))
    )
    (comp (ref "U$215")
      (value "WS2812-2020")
      (footprint "eagle-import:WS2812-2020")
      (libsource (lib "eagle-import") (part "WS2812-2020"))
    )
    (comp (ref "U$216")
      (value "WS2812-2020")
      (footprint "eagle-import:WS2812-2020")
      (libsource (lib "eagle-import") (part "WS2812-2020"))
    )
    (comp (ref "U$217")
      (value "WS2812-2020")
      (footprint "eagle-import:WS2812-2020")
      (libsource (lib "eagle-import") (part "WS2812-2020"))
    )
    (comp (ref "U$218")
      (value "WS2812-2020")
      (footprint "eagle-import:WS2812-2020")
      (libsource (lib "eagle-import") (part "WS2812-2020"))
    )
    (comp (ref "U$219")
      (value "WS2812-2020")
      (footprint "eagle-import:WS2812-2020")
      (libsource (lib "eagle-import") (part "WS2812-2020"))
    )
    (comp (ref "U$220")
      (value "WS2812-2020")
      (footprint "eagle-import:WS2812-2020")
      (libsource (lib "eagle-import") (part "WS2812-2020"))
    )
    (comp (ref "U$221")
      (value "WS2812-2020")
      (footprint "eagle-import:WS2812-2020")
      (libsource (lib "eagle-import") (part "WS2812-2020"))
    )
    (comp (ref "U$222")
      (value "WS2812-2020")
      (footprint "eagle-import:WS2812-2020")
      (libsource (lib "eagle-import") (part "WS2812-2020"))
    )
    (comp (ref "U$223")
      (value "WS2812-2020")
      (footprint "eagle-import:WS2812-2020")
      (libsource (lib "eagle-import") (part "WS2812-2020"))
    )
    (comp (ref "U$224")
      (value "WS2812-2020")
      (footprint "eagle-import:WS2812-2020")
      (libsource (lib "eagle-import") (part "WS2812-2020"))
    )
    (comp (ref "U$225")
      (value "WS2812-2020")
      (footprint "eagle-import:WS2812-2020")
      (libsource (lib "eagle-import") (part "WS2812-2020"))
    )
    (comp (ref "U$226")
      (value "WS2812-2020")
      (footprint "eagle-import:WS2812-2020")
      (libsource (lib "eagle-import") (part "WS2812-2020"))
    )
    (comp (ref "U$227")
      (value "WS2812-2020")
      (footprint "eagle-import:WS2812-2020")
      (libsource (lib "eagle-import") (part "WS2812-2020"))
    )
    (comp (ref "U$228")
      (value "WS2812-2020")
      (footprint "eagle-import:WS2812-2020")
      (libsource (lib "eagle-import") (part "WS2812-2020"))
    )
    (comp (ref "U$229")
      (value "WS2812-2020")
      (footprint "eagle-import:WS2812-2020")
      (libsource (lib "eagle-import") (part "WS2812-2020"))
    )
    (comp (ref "U$230")
      (value "WS2812-2020")
      (footprint "eagle-import:WS2812-2020")
      (libsource (lib "eagle-import") (part "WS2812-2020"))
    )
    (comp (ref "U$231")
      (value "WS2812-2020")
      (footprint "eagle-import:WS2812-2020")
      (libsource (lib "eagle-import") (part "WS2812-2020"))
    )
    (comp (ref "U$232")
      (value "WS2812-2020")
      (footprint "eagle-import:WS2812-2020")
      (libsource (lib "eagle-import") (part "WS2812-2020"))
    )
    (comp (ref "U$233")
      (value "WS2812-2020")
      (footprint "eagle-import:WS2812-2020")
      (libsource (lib "eagle-import") (part "WS2812-2020"))
    )
    (comp (ref "U$234")
      (value "WS2812-2020")
      (footprint "eagle-import:WS2812-2020")
      (libsource (lib "eagle-import") (part "WS2812-2020"))
    )
    (comp (ref "U$235")
      (value "WS2812-2020")
      (footprint "eagle-import:WS2812-2020")
      (libsource (lib "eagle-import") (part "WS2812-2020"))
    )
    (comp (ref "U$236")
      (value "WS2812-2020")
      (footprint "eagle-import:WS2812-2020")
      (libsource (lib "eagle-import") (part "WS2812-2020"))
    )
    (comp (ref "U$237")
      (value "WS2812-2020")
      (footprint "eagle-import:WS2812-2020")
      (libsource (lib "eagle-import") (part "WS2812-2020"))
    )
    (comp (ref "U$238")
      (value "WS2812-2020")
      (footprint "eagle-import:WS2812-2020")
      (libsource (lib "eagle-import") (part "WS2812-2020"))
    )
    (comp (ref "U$239")
      (value "WS2812-2020")
      (footprint "eagle-import:WS2812-2020")
      (libsource (lib "eagle-import") (part "WS2812-2020"))
    )
    (comp (ref "U$240")
      (value "WS2812-2020")
      (footprint "eagle-import:WS2812-2020")
      (libsource (lib "eagle-import") (part "WS2812-2020"))
    )
    (comp (ref "U$241")
      (value "WS2812-2020")
      (footprint "eagle-import:WS2812-2020")
      (libsource (lib "eagle-import") (part "WS2812-2020"))
    )
    (comp (ref "U$242")
      (value "WS2812-2020")
      (footprint "eagle-import:WS2812-2020")
      (libsource (lib "eagle-import") (part "WS2812-2020"))
    )
    (comp (ref "U$243")
      (value "WS2812-2020")
      (footprint "eagle-import:WS2812-2020")
      (libsource (lib "eagle-import") (part "WS2812-2020"))
    )
    (comp (ref "U$244")
      (value "WS2812-2020")
      (footprint "eagle-import:WS2812-2020")
      (libsource (lib "eagle-import") (part "WS2812-2020"))
    )
    (comp (ref "U$245")
      (value "WS2812-2020")
      (footprint "eagle-import:WS2812-2020")
      (libsource (lib "eagle-import") (part "WS2812-2020"))
    )
    (comp (ref "U$246")
      (value "WS2812-2020")
      (footprint "eagle-import:WS2812-2020")
      (libsource (lib "eagle-import") (part "WS2812-2020"))
    )
    (comp (ref "U$247")
      (value "WS2812-2020")
      (footprint "eagle-import:WS2812-2020")
      (libsource (lib "eagle-import") (part "WS2812-2020"))
    )
    (comp (ref "U$248")
      (value "WS2812-2020")
      (footprint "eagle-import:WS2812-2020")
      (libsource (lib "eagle-import") (part "WS2812-2020"))
    )
    (comp (ref "U$249")
      (value "WS2812-2020")
      (footprint "eagle-import:WS2812-2020")
      (libsource (lib "eagle-import") (part "WS2812-2020"))
    )
    (comp (ref "U$250")
      (value "WS2812-2020")
      (footprint "eagle-import:WS2812-2020")
      (libsource (lib "eagle-import") (part "WS2812-2020"))
    )
    (comp (ref "U$251")
      (value "WS2812-2020")
      (footprint "eagle-import:WS2812-2020")
      (libsource (lib "eagle-import") (part "WS2812-2020"))
    )
    (comp (ref "U$252")
      (value "WS2812-2020")
      (footprint "eagle-import:WS2812-2020")
      (libsource (lib "eagle-import") (part "WS2812-2020"))
    )
    (comp (ref "U$253")
      (value "WS2812-2020")
      (footprint "eagle-import:WS2812-2020")
      (libsource (lib "eagle-import") (part "WS2812-2020"))
    )
    (comp (ref "U$254")
      (value "WS2812-2020")
      (footprint "eagle-import:WS2812-2020")
      (libsource (lib "eagle-import") (part "WS2812-2020"))
    )
    (comp (ref "U$255")
      (value "WS2812-2020")
      (footprint "eagle-import:WS2812-2020")
      (libsource (lib "eagle-import") (part "WS2812-2020"))
    )
    (comp (ref "U$256")
      (value "WS2812-2020")
      (footprint "eagle-import:WS2812-2020")
      (libsource (lib "eagle-import") (part "WS2812-2020"))
    )
  )
  (nets
    (net (code "1") (name "/DI") (class "Default")
      (node (ref "J1") (pin "1") (pinfunction "1_1") (pintype "passive"))
      (node (ref "U$1") (pin "3") (pinfunction "DI_3") (pintype "bidirectional"))
    )
    (net (code "2") (name "/DO") (class "Default")
      (node (ref "J1") (pin "4") (pinfunction "4_4") (pintype "passive"))
      (node (ref "U$256") (pin "1") (pinfunction "DO_1") (pintype "bidirectional"))
    )
    (net (code "3") (name "/ROW_1_OUT") (class "Default")
      (node (ref "U$32") (pin "1") (pinfunction "DO_1") (pintype "bidirectional"))
      (node (ref "U$33") (pin "3") (pinfunction "DI_3") (pintype "bidirectional"))
    )
    (net (code "4") (name "/ROW_2_OUT") (class "Default")
      (node (ref "U$64") (pin "1") (pinfunction "DO_1") (pintype "bidirectional"))
      (node (ref "U$65") (pin "3") (pinfunction "DI_3") (pintype "bidirectional"))
    )
    (net (code "5") (name "/ROW_3_OUT") (class "Default")
      (node (ref "U$96") (pin "1") (pinfunction "DO_1") (pintype "bidirectional"))
      (node (ref "U$97") (pin "3") (pinfunction "DI_3") (pintype "bidirectional"))
    )
    (net (code "6") (name "/ROW_4_OUT") (class "Default")
      (node (ref "U$128") (pin "1") (pinfunction "DO_1") (pintype "bidirectional"))
      (node (ref "U$129") (pin "3") (pinfunction "DI_3") (pintype "bidirectional"))
    )
    (net (code "7") (name "/ROW_5_OUT") (class "Default")
      (node (ref "U$160") (pin "1") (pinfunction "DO_1") (pintype "bidirectional"))
      (node (ref "U$161") (pin "3") (pinfunction "DI_3") (pintype "bidirectional"))
    )
    (net (code "8") (name "/ROW_6_OUT") (class "Default")
      (node (ref "U$192") (pin "1") (pinfunction "DO_1") (pintype "bidirectional"))
      (node (ref "U$193") (pin "3") (pinfunction "DI_3") (pintype "bidirectional"))
    )
    (net (code "9") (name "/ROW_7_OUT") (class "Default")
      (node (ref "U$224") (pin "1") (pinfunction "DO_1") (pintype "bidirectional"))
      (node (ref "U$225") (pin "3") (pinfunction "DI_3") (pintype "bidirectional"))
    )
    (net (code "10") (name "GND") (class "Default")
      (node (ref "J1") (pin "3") (pinfunction "3_3") (pintype "passive"))
      (node (ref "J3") (pin "1") (pinfunction "1_1") (pintype "passive"))
      (node (ref "U$1") (pin "2") (pinfunction "VSS_2") (pintype "bidirectional"))
      (node (ref "U$10") (pin "2") (pinfunction "VSS_2") (pintype "bidirectional"))
      (node (ref "U$100") (pin "2") (pinfunction "VSS_2") (pintype "bidirectional"))
      (node (ref "U$101") (pin "2") (pinfunction "VSS_2") (pintype "bidirectional"))
      (node (ref "U$102") (pin "2") (pinfunction "VSS_2") (pintype "bidirectional"))
      (node (ref "U$103") (pin "2") (pinfunction "VSS_2") (pintype "bidirectional"))
      (node (ref "U$104") (pin "2") (pinfunction "VSS_2") (pintype "bidirectional"))
      (node (ref "U$105") (pin "2") (pinfunction "VSS_2") (pintype "bidirectional"))
      (node (ref "U$106") (pin "2") (pinfunction "VSS_2") (pintype "bidirectional"))
      (node (ref "U$107") (pin "2") (pinfunction "VSS_2") (pintype "bidirectional"))
      (node (ref "U$108") (pin "2") (pinfunction "VSS_2") (pintype "bidirectional"))
      (node (ref "U$109") (pin "2") (pinfunction "VSS_2") (pintype "bidirectional"))
      (node (ref "U$11") (pin "2") (pinfunction "VSS_2") (pintype "bidirectional"))
      (node (ref "U$110") (pin "2") (pinfunction "VSS_2") (pintype "bidirectional"))
      (node (ref "U$111") (pin "2") (pinfunction "VSS_2") (pintype "bidirectional"))
      (node (ref "U$112") (pin "2") (pinfunction "VSS_2") (pintype "bidirectional"))
      (node (ref "U$113") (pin "2") (pinfunction "VSS_2") (pintype "bidirectional"))
      (node (ref "U$114") (pin "2") (pinfunction "VSS_2") (pintype "bidirectional"))
      (node (ref "U$115") (pin "2") (pinfunction "VSS_2") (pintype "bidirectional"))
      (node (ref "U$116") (pin "2") (pinfunction "VSS_2") (pintype "bidirectional"))
      (node (ref "U$117") (pin "2") (pinfunction "VSS_2") (pintype "bidirectional"))
      (node (ref "U$118") (pin "2") (pinfunction "VSS_2") (pintype "bidirectional"))
      (node (ref "U$119") (pin "2") (pinfunction "VSS_2") (pintype "bidirectional"))
      (node (ref "U$12") (pin "2") (pinfunction "VSS_2") (pintype "bidirectional"))
      (node (ref "U$120") (pin "2") (pinfunction "VSS_2") (pintype "bidirectional"))
      (node (ref "U$121") (pin "2") (pinfunction "VSS_2") (pintype "bidirectional"))
      (node (ref "U$122") (pin "2") (pinfunction "VSS_2") (pintype "bidirectional"))
      (node (ref "U$123") (pin "2") (pinfunction "VSS_2") (pintype "bidirectional"))
      (node (ref "U$124") (pin "2") (pinfunction "VSS_2") (pintype "bidirectional"))
      (node (ref "U$125") (pin "2") (pinfunction "VSS_2") (pintype "bidirectional"))
      (node (ref "U$126") (pin "2") (pinfunction "VSS_2") (pintype "bidirectional"))
      (node (ref "U$127") (pin "2") (pinfunction "VSS_2") (pintype "bidirectional"))
      (node (ref "U$128") (pin "2") (pinfunction "VSS_2") (pintype "bidirectional"))
      (node (ref "U$129") (pin "2") (pinfunction "VSS_2") (pintype "bidirectional"))
      (node (ref "U$13") (pin "2") (pinfunction "VSS_2") (pintype "bidirectional"))
      (node (ref "U$130") (pin "2") (pinfunction "VSS_2") (pintype "bidirectional"))
      (node (ref "U$131") (pin "2") (pinfunction "VSS_2") (pintype "bidirectional"))
      (node (ref "U$132") (pin "2") (pinfunction "VSS_2") (pintype "bidirectional"))
      (node (ref "U$133") (pin "2") (pinfunction "VSS_2") (pintype "bidirectional"))
      (node (ref "U$134") (pin "2") (pinfunction "VSS_2") (pintype "bidirectional"))
      (node (ref "U$135") (pin "2") (pinfunction "VSS_2") (pintype "bidirectional"))
      (node (ref "U$136") (pin "2") (pinfunction "VSS_2") (pintype "bidirectional"))
      (node (ref "U$137") (pin "2") (pinfunction "VSS_2") (pintype "bidirectional"))
      (node (ref "U$138") (pin "2") (pinfunction "VSS_2") (pintype "bidirectional"))
      (node (ref "U$139") (pin "2") (pinfunction "VSS_2") (pintype "bidirectional"))
      (node (ref "U$14") (pin "2") (pinfunction "VSS_2") (pintype "bidirectional"))
      (node (ref "U$140") (pin "2") (pinfunction "VSS_2") (pintype "bidirectional"))
      (node (ref "U$141") (pin "2") (pinfunction "VSS_2") (pintype "bidirectional"))
      (node (ref "U$142") (pin "2") (pinfunction "VSS_2") (pintype "bidirectional"))
      (node (ref "U$143") (pin "2") (pinfunction "VSS_2") (pintype "bidirectional"))
      (node (ref "U$144") (pin "2") (pinfunction "VSS_2") (pintype "bidirectional"))
      (node (ref "U$145") (pin "2") (pinfunction "VSS_2") (pintype "bidirectional"))
      (node (ref "U$146") (pin "2") (pinfunction "VSS_2") (pintype "bidirectional"))
      (node (ref "U$147") (pin "2") (pinfunction "VSS_2") (pintype "bidirectional"))
      (node (ref "U$148") (pin "2") (pinfunction "VSS_2") (pintype "bidirectional"))
      (node (ref "U$149") (pin "2") (pinfunction "VSS_2") (pintype "bidirectional"))
      (node (ref "U$15") (pin "2") (pinfunction "VSS_2") (pintype "bidirectional"))
      (node (ref "U$150") (pin "2") (pinfunction "VSS_2") (pintype "bidirectional"))
      (node (ref "U$151") (pin "2") (pinfunction "VSS_2") (pintype "bidirectional"))
      (node (ref "U$152") (pin "2") (pinfunction "VSS_2") (pintype "bidirectional"))
      (node (ref "U$153") (pin "2") (pinfunction "VSS_2") (pintype "bidirectional"))
      (node (ref "U$154") (pin "2") (pinfunction "VSS_2") (pintype "bidirectional"))
      (node (ref "U$155") (pin "2") (pinfunction "VSS_2") (pintype "bidirectional"))
      (node (ref "U$156") (pin "2") (pinfunction "VSS_2") (pintype "bidirectional"))
      (node (ref "U$157") (pin "2") (pinfunction "VSS_2") (pintype "bidirectional"))
      (node (ref "U$158") (pin "2") (pinfunction "VSS_2") (pintype "bidirectional"))
      (node (ref "U$159") (pin "2") (pinfunction "VSS_2") (pintype "bidirectional"))
      (node (ref "U$16") (pin "2") (pinfunction "VSS_2") (pintype "bidirectional"))
      (node (ref "U$160") (pin "2") (pinfunction "VSS_2") (pintype "bidirectional"))
      (node (ref "U$161") (pin "2") (pinfunction "VSS_2") (pintype "bidirectional"))
      (node (ref "U$162") (pin "2") (pinfunction "VSS_2") (pintype "bidirectional"))
      (node (ref "U$163") (pin "2") (pinfunction "VSS_2") (pintype "bidirectional"))
      (node (ref "U$164") (pin "2") (pinfunction "VSS_2") (pintype "bidirectional"))
      (node (ref "U$165") (pin "2") (pinfunction "VSS_2") (pintype "bidirectional"))
      (node (ref "U$166") (pin "2") (pinfunction "VSS_2") (pintype "bidirectional"))
      (node (ref "U$167") (pin "2") (pinfunction "VSS_2") (pintype "bidirectional"))
      (node (ref "U$168") (pin "2") (pinfunction "VSS_2") (pintype "bidirectional"))
      (node (ref "U$169") (pin "2") (pinfunction "VSS_2") (pintype "bidirectional"))
      (node (ref "U$17") (pin "2") (pinfunction "VSS_2") (pintype "bidirectional"))
      (node (ref "U$170") (pin "2") (pinfunction "VSS_2") (pintype "bidirectional"))
      (node (ref "U$171") (pin "2") (pinfunction "VSS_2") (pintype "bidirectional"))
      (node (ref "U$172") (pin "2") (pinfunction "VSS_2") (pintype "bidirectional"))
      (node (ref "U$173") (pin "2") (pinfunction "VSS_2") (pintype "bidirectional"))
      (node (ref "U$174") (pin "2") (pinfunction "VSS_2") (pintype "bidirectional"))
      (node (ref "U$175") (pin "2") (pinfunction "VSS_2") (pintype "bidirectional"))
      (node (ref "U$176") (pin "2") (pinfunction "VSS_2") (pintype "bidirectional"))
      (node (ref "U$177") (pin "2") (pinfunction "VSS_2") (pintype "bidirectional"))
      (node (ref "U$178") (pin "2") (pinfunction "VSS_2") (pintype "bidirectional"))
      (node (ref "U$179") (pin "2") (pinfunction "VSS_2") (pintype "bidirectional"))
      (node (ref "U$18") (pin "2") (pinfunction "VSS_2") (pintype "bidirectional"))
      (node (ref "U$180") (pin "2") (pinfunction "VSS_2") (pintype "bidirectional"))
      (node (ref "U$181") (pin "2") (pinfunction "VSS_2") (pintype "bidirectional"))
      (node (ref "U$182") (pin "2") (pinfunction "VSS_2") (pintype "bidirectional"))
      (node (ref "U$183") (pin "2") (pinfunction "VSS_2") (pintype "bidirectional"))
      (node (ref "U$184") (pin "2") (pinfunction "VSS_2") (pintype "bidirectional"))
      (node (ref "U$185") (pin "2") (pinfunction "VSS_2") (pintype "bidirectional"))
      (node (ref "U$186") (pin "2") (pinfunction "VSS_2") (pintype "bidirectional"))
      (node (ref "U$187") (pin "2") (pinfunction "VSS_2") (pintype "bidirectional"))
      (node (ref "U$188") (pin "2") (pinfunction "VSS_2") (pintype "bidirectional"))
      (node (ref "U$189") (pin "2") (pinfunction "VSS_2") (pintype "bidirectional"))
      (node (ref "U$19") (pin "2") (pinfunction "VSS_2") (pintype "bidirectional"))
      (node (ref "U$190") (pin "2") (pinfunction "VSS_2") (pintype "bidirectional"))
      (node (ref "U$191") (pin "2") (pinfunction "VSS_2") (pintype "bidirectional"))
      (node (ref "U$192") (pin "2") (pinfunction "VSS_2") (pintype "bidirectional"))
      (node (ref "U$193") (pin "2") (pinfunction "VSS_2") (pintype "bidirectional"))
      (node (ref "U$194") (pin "2") (pinfunction "VSS_2") (pintype "bidirectional"))
      (node (ref "U$195") (pin "2") (pinfunction "VSS_2") (pintype "bidirectional"))
      (node (ref "U$196") (pin "2") (pinfunction "VSS_2") (pintype "bidirectional"))
      (node (ref "U$197") (pin "2") (pinfunction "VSS_2") (pintype "bidirectional"))
      (node (ref "U$198") (pin "2") (pinfunction "VSS_2") (pintype "bidirectional"))
      (node (ref "U$199") (pin "2") (pinfunction "VSS_2") (pintype "bidirectional"))
      (node (ref "U$2") (pin "2") (pinfunction "VSS_2") (pintype "bidirectional"))
      (node (ref "U$20") (pin "2") (pinfunction "VSS_2") (pintype "bidirectional"))
      (node (ref "U$200") (pin "2") (pinfunction "VSS_2") (pintype "bidirectional"))
      (node (ref "U$201") (pin "2") (pinfunction "VSS_2") (pintype "bidirectional"))
      (node (ref "U$202") (pin "2") (pinfunction "VSS_2") (pintype "bidirectional"))
      (node (ref "U$203") (pin "2") (pinfunction "VSS_2") (pintype "bidirectional"))
      (node (ref "U$204") (pin "2") (pinfunction "VSS_2") (pintype "bidirectional"))
      (node (ref "U$205") (pin "2") (pinfunction "VSS_2") (pintype "bidirectional"))
      (node (ref "U$206") (pin "2") (pinfunction "VSS_2") (pintype "bidirectional"))
      (node (ref "U$207") (pin "2") (pinfunction "VSS_2") (pintype "bidirectional"))
      (node (ref "U$208") (pin "2") (pinfunction "VSS_2") (pintype "bidirectional"))
      (node (ref "U$209") (pin "2") (pinfunction "VSS_2") (pintype "bidirectional"))
      (node (ref "U$21") (pin "2") (pinfunction "VSS_2") (pintype "bidirectional"))
      (node (ref "U$210") (pin "2") (pinfunction "VSS_2") (pintype "bidirectional"))
      (node (ref "U$211") (pin "2") (pinfunction "VSS_2") (pintype "bidirectional"))
      (node (ref "U$212") (pin "2") (pinfunction "VSS_2") (pintype "bidirectional"))
      (node (ref "U$213") (pin "2") (pinfunction "VSS_2") (pintype "bidirectional"))
      (node (ref "U$214") (pin "2") (pinfunction "VSS_2") (pintype "bidirectional"))
      (node (ref "U$215") (pin "2") (pinfunction "VSS_2") (pintype "bidirectional"))
      (node (ref "U$216") (pin "2") (pinfunction "VSS_2") (pintype "bidirectional"))
      (node (ref "U$217") (pin "2") (pinfunction "VSS_2") (pintype "bidirectional"))
      (node (ref "U$218") (pin "2") (pinfunction "VSS_2") (pintype "bidirectional"))
      (node (ref "U$219") (pin "2") (pinfunction "VSS_2") (pintype "bidirectional"))
      (node (ref "U$22") (pin "2") (pinfunction "VSS_2") (pintype "bidirectional"))
      (node (ref "U$220") (pin "2") (pinfunction "VSS_2") (pintype "bidirectional"))
      (node (ref "U$221") (pin "2") (pinfunction "VSS_2") (pintype "bidirectional"))
      (node (ref "U$222") (pin "2") (pinfunction "VSS_2") (pintype "bidirectional"))
      (node (ref "U$223") (pin "2") (pinfunction "VSS_2") (pintype "bidirectional"))
      (node (ref "U$224") (pin "2") (pinfunction "VSS_2") (pintype "bidirectional"))
      (node (ref "U$225") (pin "2") (pinfunction "VSS_2") (pintype "bidirectional"))
      (node (ref "U$226") (pin "2") (pinfunction "VSS_2") (pintype "bidirectional"))
      (node (ref "U$227") (pin "2") (pinfunction "VSS_2") (pintype "bidirectional"))
      (node (ref "U$228") (pin "2") (pinfunction "VSS_2") (pintype "bidirectional"))
      (node (ref "U$229") (pin "2") (pinfunction "VSS_2") (pintype "bidirectional"))
      (node (ref "U$23") (pin "2") (pinfunction "VSS_2") (pintype "bidirectional"))
      (node (ref "U$230") (pin "2") (pinfunction "VSS_2") (pintype "bidirectional"))
      (node (ref "U$231") (pin "2") (pinfunction "VSS_2") (pintype "bidirectional"))
      (node (ref "U$232") (pin "2") (pinfunction "VSS_2") (pintype "bidirectional"))
      (node (ref "U$233") (pin "2") (pinfunction "VSS_2") (pintype "bidirectional"))
      (node (ref "U$234") (pin "2") (pinfunction "VSS_2") (pintype "bidirectional"))
      (node (ref "U$235") (pin "2") (pinfunction "VSS_2") (pintype "bidirectional"))
      (node (ref "U$236") (pin "2") (pinfunction "VSS_2") (pintype "bidirectional"))
      (node (ref "U$237") (pin "2") (pinfunction "VSS_2") (pintype "bidirectional"))
      (node (ref "U$238") (pin "2") (pinfunction "VSS_2") (pintype "bidirectional"))
      (node (ref "U$239") (pin "2") (pinfunction "VSS_2") (pintype "bidirectional"))
      (node (ref "U$24") (pin "2") (pinfunction "VSS_2") (pintype "bidirectional"))
      (node (ref "U$240") (pin "2") (pinfunction "VSS_2") (pintype "bidirectional"))
      (node (ref "U$241") (pin "2") (pinfunction "VSS_2") (pintype "bidirectional"))
      (node (ref "U$242") (pin "2") (pinfunction "VSS_2") (pintype "bidirectional"))
      (node (ref "U$243") (pin "2") (pinfunction "VSS_2") (pintype "bidirectional"))
      (node (ref "U$244") (pin "2") (pinfunction "VSS_2") (pintype "bidirectional"))
      (node (ref "U$245") (pin "2") (pinfunction "VSS_2") (pintype "bidirectional"))
      (node (ref "U$246") (pin "2") (pinfunction "VSS_2") (pintype "bidirectional"))
      (node (ref "U$247") (pin "2") (pinfunction "VSS_2") (pintype "bidirectional"))
      (node (ref "U$248") (pin "2") (pinfunction "VSS_2") (pintype "bidirectional"))
      (node (ref "U$249") (pin "2") (pinfunction "VSS_2") (pintype "bidirectional"))
      (node (ref "U$25") (pin "2") (pinfunction "VSS_2") (pintype "bidirectional"))
      (node (ref "U$250") (pin "2") (pinfunction "VSS_2") (pintype "bidirectional"))
      (node (ref "U$251") (pin "2") (pinfunction "VSS_2") (pintype "bidirectional"))
      (node (ref "U$252") (pin "2") (pinfunction "VSS_2") (pintype "bidirectional"))
      (node (ref "U$253") (pin "2") (pinfunction "VSS_2") (pintype "bidirectional"))
      (node (ref "U$254") (pin "2") (pinfunction "VSS_2") (pintype "bidirectional"))
      (node (ref "U$255") (pin "2") (pinfunction "VSS_2") (pintype "bidirectional"))
      (node (ref "U$256") (pin "2") (pinfunction "VSS_2") (pintype "bidirectional"))
      (node (ref "U$26") (pin "2") (pinfunction "VSS_2") (pintype "bidirectional"))
      (node (ref "U$27") (pin "2") (pinfunction "VSS_2") (pintype "bidirectional"))
      (node (ref "U$28") (pin "2") (pinfunction "VSS_2") (pintype "bidirectional"))
      (node (ref "U$29") (pin "2") (pinfunction "VSS_2") (pintype "bidirectional"))
      (node (ref "U$3") (pin "2") (pinfunction "VSS_2") (pintype "bidirectional"))
      (node (ref "U$30") (pin "2") (pinfunction "VSS_2") (pintype "bidirectional"))
      (node (ref "U$31") (pin "2") (pinfunction "VSS_2") (pintype "bidirectional"))
      (node (ref "U$32") (pin "2") (pinfunction "VSS_2") (pintype "bidirectional"))
      (node (ref "U$33") (pin "2") (pinfunction "VSS_2") (pintype "bidirectional"))
      (node (ref "U$34") (pin "2") (pinfunction "VSS_2") (pintype "bidirectional"))
      (node (ref "U$35") (pin "2") (pinfunction "VSS_2") (pintype "bidirectional"))
      (node (ref "U$36") (pin "2") (pinfunction "VSS_2") (pintype "bidirectional"))
      (node (ref "U$37") (pin "2") (pinfunction "VSS_2") (pintype "bidirectional"))
      (node (ref "U$38") (pin "2") (pinfunction "VSS_2") (pintype "bidirectional"))
      (node (ref "U$39") (pin "2") (pinfunction "VSS_2") (pintype "bidirectional"))
      (node (ref "U$4") (pin "2") (pinfunction "VSS_2") (pintype "bidirectional"))
      (node (ref "U$40") (pin "2") (pinfunction "VSS_2") (pintype "bidirectional"))
      (node (ref "U$41") (pin "2") (pinfunction "VSS_2") (pintype "bidirectional"))
      (node (ref "U$42") (pin "2") (pinfunction "VSS_2") (pintype "bidirectional"))
      (node (ref "U$43") (pin "2") (pinfunction "VSS_2") (pintype "bidirectional"))
      (node (ref "U$44") (pin "2") (pinfunction "VSS_2") (pintype "bidirectional"))
      (node (ref "U$45") (pin "2") (pinfunction "VSS_2") (pintype "bidirectional"))
      (node (ref "U$46") (pin "2") (pinfunction "VSS_2") (pintype "bidirectional"))
      (node (ref "U$47") (pin "2") (pinfunction "VSS_2") (pintype "bidirectional"))
      (node (ref "U$48") (pin "2") (pinfunction "VSS_2") (pintype "bidirectional"))
      (node (ref "U$49") (pin "2") (pinfunction "VSS_2") (pintype "bidirectional"))
      (node (ref "U$5") (pin "2") (pinfunction "VSS_2") (pintype "bidirectional"))
      (node (ref "U$50") (pin "2") (pinfunction "VSS_2") (pintype "bidirectional"))
      (node (ref "U$51") (pin "2") (pinfunction "VSS_2") (pintype "bidirectional"))
      (node (ref "U$52") (pin "2") (pinfunction "VSS_2") (pintype "bidirectional"))
      (node (ref "U$53") (pin "2") (pinfunction "VSS_2") (pintype "bidirectional"))
      (node (ref "U$54") (pin "2") (pinfunction "VSS_2") (pintype "bidirectional"))
      (node (ref "U$55") (pin "2") (pinfunction "VSS_2") (pintype "bidirectional"))
      (node (ref "U$56") (pin "2") (pinfunction "VSS_2") (pintype "bidirectional"))
      (node (ref "U$57") (pin "2") (pinfunction "VSS_2") (pintype "bidirectional"))
      (node (ref "U$58") (pin "2") (pinfunction "VSS_2") (pintype "bidirectional"))
      (node (ref "U$59") (pin "2") (pinfunction "VSS_2") (pintype "bidirectional"))
      (node (ref "U$6") (pin "2") (pinfunction "VSS_2") (pintype "bidirectional"))
      (node (ref "U$60") (pin "2") (pinfunction "VSS_2") (pintype "bidirectional"))
      (node (ref "U$61") (pin "2") (pinfunction "VSS_2") (pintype "bidirectional"))
      (node (ref "U$62") (pin "2") (pinfunction "VSS_2") (pintype "bidirectional"))
      (node (ref "U$63") (pin "2") (pinfunction "VSS_2") (pintype "bidirectional"))
      (node (ref "U$64") (pin "2") (pinfunction "VSS_2") (pintype "bidirectional"))
      (node (ref "U$65") (pin "2") (pinfunction "VSS_2") (pintype "bidirectional"))
      (node (ref "U$66") (pin "2") (pinfunction "VSS_2") (pintype "bidirectional"))
      (node (ref "U$67") (pin "2") (pinfunction "VSS_2") (pintype "bidirectional"))
      (node (ref "U$68") (pin "2") (pinfunction "VSS_2") (pintype "bidirectional"))
      (node (ref "U$69") (pin "2") (pinfunction "VSS_2") (pintype "bidirectional"))
      (node (ref "U$7") (pin "2") (pinfunction "VSS_2") (pintype "bidirectional"))
      (node (ref "U$70") (pin "2") (pinfunction "VSS_2") (pintype "bidirectional"))
      (node (ref "U$71") (pin "2") (pinfunction "VSS_2") (pintype "bidirectional"))
      (node (ref "U$72") (pin "2") (pinfunction "VSS_2") (pintype "bidirectional"))
      (node (ref "U$73") (pin "2") (pinfunction "VSS_2") (pintype "bidirectional"))
      (node (ref "U$74") (pin "2") (pinfunction "VSS_2") (pintype "bidirectional"))
      (node (ref "U$75") (pin "2") (pinfunction "VSS_2") (pintype "bidirectional"))
      (node (ref "U$76") (pin "2") (pinfunction "VSS_2") (pintype "bidirectional"))
      (node (ref "U$77") (pin "2") (pinfunction "VSS_2") (pintype "bidirectional"))
      (node (ref "U$78") (pin "2") (pinfunction "VSS_2") (pintype "bidirectional"))
      (node (ref "U$79") (pin "2") (pinfunction "VSS_2") (pintype "bidirectional"))
      (node (ref "U$8") (pin "2") (pinfunction "VSS_2") (pintype "bidirectional"))
      (node (ref "U$80") (pin "2") (pinfunction "VSS_2") (pintype "bidirectional"))
      (node (ref "U$81") (pin "2") (pinfunction "VSS_2") (pintype "bidirectional"))
      (node (ref "U$82") (pin "2") (pinfunction "VSS_2") (pintype "bidirectional"))
      (node (ref "U$83") (pin "2") (pinfunction "VSS_2") (pintype "bidirectional"))
      (node (ref "U$84") (pin "2") (pinfunction "VSS_2") (pintype "bidirectional"))
      (node (ref "U$85") (pin "2") (pinfunction "VSS_2") (pintype "bidirectional"))
      (node (ref "U$86") (pin "2") (pinfunction "VSS_2") (pintype "bidirectional"))
      (node (ref "U$87") (pin "2") (pinfunction "VSS_2") (pintype "bidirectional"))
      (node (ref "U$88") (pin "2") (pinfunction "VSS_2") (pintype "bidirectional"))
      (node (ref "U$89") (pin "2") (pinfunction "VSS_2") (pintype "bidirectional"))
      (node (ref "U$9") (pin "2") (pinfunction "VSS_2") (pintype "bidirectional"))
      (node (ref "U$90") (pin "2") (pinfunction "VSS_2") (pintype "bidirectional"))
      (node (ref "U$91") (pin "2") (pinfunction "VSS_2") (pintype "bidirectional"))
      (node (ref "U$92") (pin "2") (pinfunction "VSS_2") (pintype "bidirectional"))
      (node (ref "U$93") (pin "2") (pinfunction "VSS_2") (pintype "bidirectional"))
      (node (ref "U$94") (pin "2") (pinfunction "VSS_2") (pintype "bidirectional"))
      (node (ref "U$95") (pin "2") (pinfunction "VSS_2") (pintype "bidirectional"))
      (node (ref "U$96") (pin "2") (pinfunction "VSS_2") (pintype "bidirectional"))
      (node (ref "U$97") (pin "2") (pinfunction "VSS_2") (pintype "bidirectional"))
      (node (ref "U$98") (pin "2") (pinfunction "VSS_2") (pintype "bidirectional"))
      (node (ref "U$99") (pin "2") (pinfunction "VSS_2") (pintype "bidirectional"))
    )
    (net (code "11") (name "Net-(U$1-DO)") (class "Default")
      (node (ref "U$1") (pin "1") (pinfunction "DO_1") (pintype "bidirectional"))
      (node (ref "U$2") (pin "3") (pinfunction "DI_3") (pintype "bidirectional"))
    )
    (net (code "12") (name "Net-(U$2-DO)") (class "Default")
      (node (ref "U$2") (pin "1") (pinfunction "DO_1") (pintype "bidirectional"))
      (node (ref "U$3") (pin "3") (pinfunction "DI_3") (pintype "bidirectional"))
    )
    (net (code "13") (name "Net-(U$3-DO)") (class "Default")
      (node (ref "U$3") (pin "1") (pinfunction "DO_1") (pintype "bidirectional"))
      (node (ref "U$4") (pin "3") (pinfunction "DI_3") (pintype "bidirectional"))
    )
    (net (code "14") (name "Net-(U$4-DO)") (class "Default")
      (node (ref "U$4") (pin "1") (pinfunction "DO_1") (pintype "bidirectional"))
      (node (ref "U$5") (pin "3") (pinfunction "DI_3") (pintype "bidirectional"))
    )
    (net (code "15") (name "Net-(U$5-DO)") (class "Default")
      (node (ref "U$5") (pin "1") (pinfunction "DO_1") (pintype "bidirectional"))
      (node (ref "U$6") (pin "3") (pinfunction "DI_3") (pintype "bidirectional"))
    )
    (net (code "16") (name "Net-(U$6-DO)") (class "Default")
      (node (ref "U$6") (pin "1") (pinfunction "DO_1") (pintype "bidirectional"))
      (node (ref "U$7") (pin "3") (pinfunction "DI_3") (pintype "bidirectional"))
    )
    (net (code "17") (name "Net-(U$7-DO)") (class "Default")
      (node (ref "U$7") (pin "1") (pinfunction "DO_1") (pintype "bidirectional"))
      (node (ref "U$8") (pin "3") (pinfunction "DI_3") (pintype "bidirectional"))
    )
    (net (code "18") (name "Net-(U$8-DO)") (class "Default")
      (node (ref "U$8") (pin "1") (pinfunction "DO_1") (pintype "bidirectional"))
      (node (ref "U$9") (pin "3") (pinfunction "DI_3") (pintype "bidirectional"))
    )
    (net (code "19") (name "Net-(U$10-DI)") (class "Default")
      (node (ref "U$10") (pin "3") (pinfunction "DI_3") (pintype "bidirectional"))
      (node (ref "U$9") (pin "1") (pinfunction "DO_1") (pintype "bidirectional"))
    )
    (net (code "20") (name "Net-(U$10-DO)") (class "Default")
      (node (ref "U$10") (pin "1") (pinfunction "DO_1") (pintype "bidirectional"))
      (node (ref "U$11") (pin "3") (pinfunction "DI_3") (pintype "bidirectional"))
    )
    (net (code "21") (name "Net-(U$11-DO)") (class "Default")
      (node (ref "U$11") (pin "1") (pinfunction "DO_1") (pintype "bidirectional"))
      (node (ref "U$12") (pin "3") (pinfunction "DI_3") (pintype "bidirectional"))
    )
    (net (code "22") (name "Net-(U$12-DO)") (class "Default")
      (node (ref "U$12") (pin "1") (pinfunction "DO_1") (pintype "bidirectional"))
      (node (ref "U$13") (pin "3") (pinfunction "DI_3") (pintype "bidirectional"))
    )
    (net (code "23") (name "Net-(U$13-DO)") (class "Default")
      (node (ref "U$13") (pin "1") (pinfunction "DO_1") (pintype "bidirectional"))
      (node (ref "U$14") (pin "3") (pinfunction "DI_3") (pintype "bidirectional"))
    )
    (net (code "24") (name "Net-(U$14-DO)") (class "Default")
      (node (ref "U$14") (pin "1") (pinfunction "DO_1") (pintype "bidirectional"))
      (node (ref "U$15") (pin "3") (pinfunction "DI_3") (pintype "bidirectional"))
    )
    (net (code "25") (name "Net-(U$15-DO)") (class "Default")
      (node (ref "U$15") (pin "1") (pinfunction "DO_1") (pintype "bidirectional"))
      (node (ref "U$16") (pin "3") (pinfunction "DI_3") (pintype "bidirectional"))
    )
    (net (code "26") (name "Net-(U$16-DO)") (class "Default")
      (node (ref "U$16") (pin "1") (pinfunction "DO_1") (pintype "bidirectional"))
      (node (ref "U$17") (pin "3") (pinfunction "DI_3") (pintype "bidirectional"))
    )
    (net (code "27") (name "Net-(U$17-DO)") (class "Default")
      (node (ref "U$17") (pin "1") (pinfunction "DO_1") (pintype "bidirectional"))
      (node (ref "U$18") (pin "3") (pinfunction "DI_3") (pintype "bidirectional"))
    )
    (net (code "28") (name "Net-(U$18-DO)") (class "Default")
      (node (ref "U$18") (pin "1") (pinfunction "DO_1") (pintype "bidirectional"))
      (node (ref "U$19") (pin "3") (pinfunction "DI_3") (pintype "bidirectional"))
    )
    (net (code "29") (name "Net-(U$19-DO)") (class "Default")
      (node (ref "U$19") (pin "1") (pinfunction "DO_1") (pintype "bidirectional"))
      (node (ref "U$20") (pin "3") (pinfunction "DI_3") (pintype "bidirectional"))
    )
    (net (code "30") (name "Net-(U$20-DO)") (class "Default")
      (node (ref "U$20") (pin "1") (pinfunction "DO_1") (pintype "bidirectional"))
      (node (ref "U$21") (pin "3") (pinfunction "DI_3") (pintype "bidirectional"))
    )
    (net (code "31") (name "Net-(U$21-DO)") (class "Default")
      (node (ref "U$21") (pin "1") (pinfunction "DO_1") (pintype "bidirectional"))
      (node (ref "U$22") (pin "3") (pinfunction "DI_3") (pintype "bidirectional"))
    )
    (net (code "32") (name "Net-(U$22-DO)") (class "Default")
      (node (ref "U$22") (pin "1") (pinfunction "DO_1") (pintype "bidirectional"))
      (node (ref "U$23") (pin "3") (pinfunction "DI_3") (pintype "bidirectional"))
    )
    (net (code "33") (name "Net-(U$23-DO)") (class "Default")
      (node (ref "U$23") (pin "1") (pinfunction "DO_1") (pintype "bidirectional"))
      (node (ref "U$24") (pin "3") (pinfunction "DI_3") (pintype "bidirectional"))
    )
    (net (code "34") (name "Net-(U$24-DO)") (class "Default")
      (node (ref "U$24") (pin "1") (pinfunction "DO_1") (pintype "bidirectional"))
      (node (ref "U$25") (pin "3") (pinfunction "DI_3") (pintype "bidirectional"))
    )
    (net (code "35") (name "Net-(U$25-DO)") (class "Default")
      (node (ref "U$25") (pin "1") (pinfunction "DO_1") (pintype "bidirectional"))
      (node (ref "U$26") (pin "3") (pinfunction "DI_3") (pintype "bidirectional"))
    )
    (net (code "36") (name "Net-(U$26-DO)") (class "Default")
      (node (ref "U$26") (pin "1") (pinfunction "DO_1") (pintype "bidirectional"))
      (node (ref "U$27") (pin "3") (pinfunction "DI_3") (pintype "bidirectional"))
    )
    (net (code "37") (name "Net-(U$27-DO)") (class "Default")
      (node (ref "U$27") (pin "1") (pinfunction "DO_1") (pintype "bidirectional"))
      (node (ref "U$28") (pin "3") (pinfunction "DI_3") (pintype "bidirectional"))
    )
    (net (code "38") (name "Net-(U$28-DO)") (class "Default")
      (node (ref "U$28") (pin "1") (pinfunction "DO_1") (pintype "bidirectional"))
      (node (ref "U$29") (pin "3") (pinfunction "DI_3") (pintype "bidirectional"))
    )
    (net (code "39") (name "Net-(U$29-DO)") (class "Default")
      (node (ref "U$29") (pin "1") (pinfunction "DO_1") (pintype "bidirectional"))
      (node (ref "U$30") (pin "3") (pinfunction "DI_3") (pintype "bidirectional"))
    )
    (net (code "40") (name "Net-(U$30-DO)") (class "Default")
      (node (ref "U$30") (pin "1") (pinfunction "DO_1") (pintype "bidirectional"))
      (node (ref "U$31") (pin "3") (pinfunction "DI_3") (pintype "bidirectional"))
    )
    (net (code "41") (name "Net-(U$31-DO)") (class "Default")
      (node (ref "U$31") (pin "1") (pinfunction "DO_1") (pintype "bidirectional"))
      (node (ref "U$32") (pin "3") (pinfunction "DI_3") (pintype "bidirectional"))
    )
    (net (code "42") (name "Net-(U$33-DO)") (class "Default")
      (node (ref "U$33") (pin "1") (pinfunction "DO_1") (pintype "bidirectional"))
      (node (ref "U$34") (pin "3") (pinfunction "DI_3") (pintype "bidirectional"))
    )
    (net (code "43") (name "Net-(U$34-DO)") (class "Default")
      (node (ref "U$34") (pin "1") (pinfunction "DO_1") (pintype "bidirectional"))
      (node (ref "U$35") (pin "3") (pinfunction "DI_3") (pintype "bidirectional"))
    )
    (net (code "44") (name "Net-(U$35-DO)") (class "Default")
      (node (ref "U$35") (pin "1") (pinfunction "DO_1") (pintype "bidirectional"))
      (node (ref "U$36") (pin "3") (pinfunction "DI_3") (pintype "bidirectional"))
    )
    (net (code "45") (name "Net-(U$36-DO)") (class "Default")
      (node (ref "U$36") (pin "1") (pinfunction "DO_1") (pintype "bidirectional"))
      (node (ref "U$37") (pin "3") (pinfunction "DI_3") (pintype "bidirectional"))
    )
    (net (code "46") (name "Net-(U$37-DO)") (class "Default")
      (node (ref "U$37") (pin "1") (pinfunction "DO_1") (pintype "bidirectional"))
      (node (ref "U$38") (pin "3") (pinfunction "DI_3") (pintype "bidirectional"))
    )
    (net (code "47") (name "Net-(U$38-DO)") (class "Default")
      (node (ref "U$38") (pin "1") (pinfunction "DO_1") (pintype "bidirectional"))
      (node (ref "U$39") (pin "3") (pinfunction "DI_3") (pintype "bidirectional"))
    )
    (net (code "48") (name "Net-(U$39-DO)") (class "Default")
      (node (ref "U$39") (pin "1") (pinfunction "DO_1") (pintype "bidirectional"))
      (node (ref "U$40") (pin "3") (pinfunction "DI_3") (pintype "bidirectional"))
    )
    (net (code "49") (name "Net-(U$40-DO)") (class "Default")
      (node (ref "U$40") (pin "1") (pinfunction "DO_1") (pintype "bidirectional"))
      (node (ref "U$41") (pin "3") (pinfunction "DI_3") (pintype "bidirectional"))
    )
    (net (code "50") (name "Net-(U$41-DO)") (class "Default")
      (node (ref "U$41") (pin "1") (pinfunction "DO_1") (pintype "bidirectional"))
      (node (ref "U$42") (pin "3") (pinfunction "DI_3") (pintype "bidirectional"))
    )
    (net (code "51") (name "Net-(U$42-DO)") (class "Default")
      (node (ref "U$42") (pin "1") (pinfunction "DO_1") (pintype "bidirectional"))
      (node (ref "U$43") (pin "3") (pinfunction "DI_3") (pintype "bidirectional"))
    )
    (net (code "52") (name "Net-(U$43-DO)") (class "Default")
      (node (ref "U$43") (pin "1") (pinfunction "DO_1") (pintype "bidirectional"))
      (node (ref "U$44") (pin "3") (pinfunction "DI_3") (pintype "bidirectional"))
    )
    (net (code "53") (name "Net-(U$44-DO)") (class "Default")
      (node (ref "U$44") (pin "1") (pinfunction "DO_1") (pintype "bidirectional"))
      (node (ref "U$45") (pin "3") (pinfunction "DI_3") (pintype "bidirectional"))
    )
    (net (code "54") (name "Net-(U$45-DO)") (class "Default")
      (node (ref "U$45") (pin "1") (pinfunction "DO_1") (pintype "bidirectional"))
      (node (ref "U$46") (pin "3") (pinfunction "DI_3") (pintype "bidirectional"))
    )
    (net (code "55") (name "Net-(U$46-DO)") (class "Default")
      (node (ref "U$46") (pin "1") (pinfunction "DO_1") (pintype "bidirectional"))
      (node (ref "U$47") (pin "3") (pinfunction "DI_3") (pintype "bidirectional"))
    )
    (net (code "56") (name "Net-(U$47-DO)") (class "Default")
      (node (ref "U$47") (pin "1") (pinfunction "DO_1") (pintype "bidirectional"))
      (node (ref "U$48") (pin "3") (pinfunction "DI_3") (pintype "bidirectional"))
    )
    (net (code "57") (name "Net-(U$48-DO)") (class "Default")
      (node (ref "U$48") (pin "1") (pinfunction "DO_1") (pintype "bidirectional"))
      (node (ref "U$49") (pin "3") (pinfunction "DI_3") (pintype "bidirectional"))
    )
    (net (code "58") (name "Net-(U$49-DO)") (class "Default")
      (node (ref "U$49") (pin "1") (pinfunction "DO_1") (pintype "bidirectional"))
      (node (ref "U$50") (pin "3") (pinfunction "DI_3") (pintype "bidirectional"))
    )
    (net (code "59") (name "Net-(U$50-DO)") (class "Default")
      (node (ref "U$50") (pin "1") (pinfunction "DO_1") (pintype "bidirectional"))
      (node (ref "U$51") (pin "3") (pinfunction "DI_3") (pintype "bidirectional"))
    )
    (net (code "60") (name "Net-(U$51-DO)") (class "Default")
      (node (ref "U$51") (pin "1") (pinfunction "DO_1") (pintype "bidirectional"))
      (node (ref "U$52") (pin "3") (pinfunction "DI_3") (pintype "bidirectional"))
    )
    (net (code "61") (name "Net-(U$52-DO)") (class "Default")
      (node (ref "U$52") (pin "1") (pinfunction "DO_1") (pintype "bidirectional"))
      (node (ref "U$53") (pin "3") (pinfunction "DI_3") (pintype "bidirectional"))
    )
    (net (code "62") (name "Net-(U$53-DO)") (class "Default")
      (node (ref "U$53") (pin "1") (pinfunction "DO_1") (pintype "bidirectional"))
      (node (ref "U$54") (pin "3") (pinfunction "DI_3") (pintype "bidirectional"))
    )
    (net (code "63") (name "Net-(U$54-DO)") (class "Default")
      (node (ref "U$54") (pin "1") (pinfunction "DO_1") (pintype "bidirectional"))
      (node (ref "U$55") (pin "3") (pinfunction "DI_3") (pintype "bidirectional"))
    )
    (net (code "64") (name "Net-(U$55-DO)") (class "Default")
      (node (ref "U$55") (pin "1") (pinfunction "DO_1") (pintype "bidirectional"))
      (node (ref "U$56") (pin "3") (pinfunction "DI_3") (pintype "bidirectional"))
    )
    (net (code "65") (name "Net-(U$56-DO)") (class "Default")
      (node (ref "U$56") (pin "1") (pinfunction "DO_1") (pintype "bidirectional"))
      (node (ref "U$57") (pin "3") (pinfunction "DI_3") (pintype "bidirectional"))
    )
    (net (code "66") (name "Net-(U$57-DO)") (class "Default")
      (node (ref "U$57") (pin "1") (pinfunction "DO_1") (pintype "bidirectional"))
      (node (ref "U$58") (pin "3") (pinfunction "DI_3") (pintype "bidirectional"))
    )
    (net (code "67") (name "Net-(U$58-DO)") (class "Default")
      (node (ref "U$58") (pin "1") (pinfunction "DO_1") (pintype "bidirectional"))
      (node (ref "U$59") (pin "3") (pinfunction "DI_3") (pintype "bidirectional"))
    )
    (net (code "68") (name "Net-(U$59-DO)") (class "Default")
      (node (ref "U$59") (pin "1") (pinfunction "DO_1") (pintype "bidirectional"))
      (node (ref "U$60") (pin "3") (pinfunction "DI_3") (pintype "bidirectional"))
    )
    (net (code "69") (name "Net-(U$60-DO)") (class "Default")
      (node (ref "U$60") (pin "1") (pinfunction "DO_1") (pintype "bidirectional"))
      (node (ref "U$61") (pin "3") (pinfunction "DI_3") (pintype "bidirectional"))
    )
    (net (code "70") (name "Net-(U$61-DO)") (class "Default")
      (node (ref "U$61") (pin "1") (pinfunction "DO_1") (pintype "bidirectional"))
      (node (ref "U$62") (pin "3") (pinfunction "DI_3") (pintype "bidirectional"))
    )
    (net (code "71") (name "Net-(U$62-DO)") (class "Default")
      (node (ref "U$62") (pin "1") (pinfunction "DO_1") (pintype "bidirectional"))
      (node (ref "U$63") (pin "3") (pinfunction "DI_3") (pintype "bidirectional"))
    )
    (net (code "72") (name "Net-(U$63-DO)") (class "Default")
      (node (ref "U$63") (pin "1") (pinfunction "DO_1") (pintype "bidirectional"))
      (node (ref "U$64") (pin "3") (pinfunction "DI_3") (pintype "bidirectional"))
    )
    (net (code "73") (name "Net-(U$65-DO)") (class "Default")
      (node (ref "U$65") (pin "1") (pinfunction "DO_1") (pintype "bidirectional"))
      (node (ref "U$66") (pin "3") (pinfunction "DI_3") (pintype "bidirectional"))
    )
    (net (code "74") (name "Net-(U$66-DO)") (class "Default")
      (node (ref "U$66") (pin "1") (pinfunction "DO_1") (pintype "bidirectional"))
      (node (ref "U$67") (pin "3") (pinfunction "DI_3") (pintype "bidirectional"))
    )
    (net (code "75") (name "Net-(U$67-DO)") (class "Default")
      (node (ref "U$67") (pin "1") (pinfunction "DO_1") (pintype "bidirectional"))
      (node (ref "U$68") (pin "3") (pinfunction "DI_3") (pintype "bidirectional"))
    )
    (net (code "76") (name "Net-(U$68-DO)") (class "Default")
      (node (ref "U$68") (pin "1") (pinfunction "DO_1") (pintype "bidirectional"))
      (node (ref "U$69") (pin "3") (pinfunction "DI_3") (pintype "bidirectional"))
    )
    (net (code "77") (name "Net-(U$69-DO)") (class "Default")
      (node (ref "U$69") (pin "1") (pinfunction "DO_1") (pintype "bidirectional"))
      (node (ref "U$70") (pin "3") (pinfunction "DI_3") (pintype "bidirectional"))
    )
    (net (code "78") (name "Net-(U$70-DO)") (class "Default")
      (node (ref "U$70") (pin "1") (pinfunction "DO_1") (pintype "bidirectional"))
      (node (ref "U$71") (pin "3") (pinfunction "DI_3") (pintype "bidirectional"))
    )
    (net (code "79") (name "Net-(U$71-DO)") (class "Default")
      (node (ref "U$71") (pin "1") (pinfunction "DO_1") (pintype "bidirectional"))
      (node (ref "U$72") (pin "3") (pinfunction "DI_3") (pintype "bidirectional"))
    )
    (net (code "80") (name "Net-(U$72-DO)") (class "Default")
      (node (ref "U$72") (pin "1") (pinfunction "DO_1") (pintype "bidirectional"))
      (node (ref "U$73") (pin "3") (pinfunction "DI_3") (pintype "bidirectional"))
    )
    (net (code "81") (name "Net-(U$73-DO)") (class "Default")
      (node (ref "U$73") (pin "1") (pinfunction "DO_1") (pintype "bidirectional"))
      (node (ref "U$74") (pin "3") (pinfunction "DI_3") (pintype "bidirectional"))
    )
    (net (code "82") (name "Net-(U$74-DO)") (class "Default")
      (node (ref "U$74") (pin "1") (pinfunction "DO_1") (pintype "bidirectional"))
      (node (ref "U$75") (pin "3") (pinfunction "DI_3") (pintype "bidirectional"))
    )
    (net (code "83") (name "Net-(U$75-DO)") (class "Default")
      (node (ref "U$75") (pin "1") (pinfunction "DO_1") (pintype "bidirectional"))
      (node (ref "U$76") (pin "3") (pinfunction "DI_3") (pintype "bidirectional"))
    )
    (net (code "84") (name "Net-(U$76-DO)") (class "Default")
      (node (ref "U$76") (pin "1") (pinfunction "DO_1") (pintype "bidirectional"))
      (node (ref "U$77") (pin "3") (pinfunction "DI_3") (pintype "bidirectional"))
    )
    (net (code "85") (name "Net-(U$77-DO)") (class "Default")
      (node (ref "U$77") (pin "1") (pinfunction "DO_1") (pintype "bidirectional"))
      (node (ref "U$78") (pin "3") (pinfunction "DI_3") (pintype "bidirectional"))
    )
    (net (code "86") (name "Net-(U$78-DO)") (class "Default")
      (node (ref "U$78") (pin "1") (pinfunction "DO_1") (pintype "bidirectional"))
      (node (ref "U$79") (pin "3") (pinfunction "DI_3") (pintype "bidirectional"))
    )
    (net (code "87") (name "Net-(U$79-DO)") (class "Default")
      (node (ref "U$79") (pin "1") (pinfunction "DO_1") (pintype "bidirectional"))
      (node (ref "U$80") (pin "3") (pinfunction "DI_3") (pintype "bidirectional"))
    )
    (net (code "88") (name "Net-(U$80-DO)") (class "Default")
      (node (ref "U$80") (pin "1") (pinfunction "DO_1") (pintype "bidirectional"))
      (node (ref "U$81") (pin "3") (pinfunction "DI_3") (pintype "bidirectional"))
    )
    (net (code "89") (name "Net-(U$81-DO)") (class "Default")
      (node (ref "U$81") (pin "1") (pinfunction "DO_1") (pintype "bidirectional"))
      (node (ref "U$82") (pin "3") (pinfunction "DI_3") (pintype "bidirectional"))
    )
    (net (code "90") (name "Net-(U$82-DO)") (class "Default")
      (node (ref "U$82") (pin "1") (pinfunction "DO_1") (pintype "bidirectional"))
      (node (ref "U$83") (pin "3") (pinfunction "DI_3") (pintype "bidirectional"))
    )
    (net (code "91") (name "Net-(U$83-DO)") (class "Default")
      (node (ref "U$83") (pin "1") (pinfunction "DO_1") (pintype "bidirectional"))
      (node (ref "U$84") (pin "3") (pinfunction "DI_3") (pintype "bidirectional"))
    )
    (net (code "92") (name "Net-(U$84-DO)") (class "Default")
      (node (ref "U$84") (pin "1") (pinfunction "DO_1") (pintype "bidirectional"))
      (node (ref "U$85") (pin "3") (pinfunction "DI_3") (pintype "bidirectional"))
    )
    (net (code "93") (name "Net-(U$85-DO)") (class "Default")
      (node (ref "U$85") (pin "1") (pinfunction "DO_1") (pintype "bidirectional"))
      (node (ref "U$86") (pin "3") (pinfunction "DI_3") (pintype "bidirectional"))
    )
    (net (code "94") (name "Net-(U$86-DO)") (class "Default")
      (node (ref "U$86") (pin "1") (pinfunction "DO_1") (pintype "bidirectional"))
      (node (ref "U$87") (pin "3") (pinfunction "DI_3") (pintype "bidirectional"))
    )
    (net (code "95") (name "Net-(U$87-DO)") (class "Default")
      (node (ref "U$87") (pin "1") (pinfunction "DO_1") (pintype "bidirectional"))
      (node (ref "U$88") (pin "3") (pinfunction "DI_3") (pintype "bidirectional"))
    )
    (net (code "96") (name "Net-(U$88-DO)") (class "Default")
      (node (ref "U$88") (pin "1") (pinfunction "DO_1") (pintype "bidirectional"))
      (node (ref "U$89") (pin "3") (pinfunction "DI_3") (pintype "bidirectional"))
    )
    (net (code "97") (name "Net-(U$89-DO)") (class "Default")
      (node (ref "U$89") (pin "1") (pinfunction "DO_1") (pintype "bidirectional"))
      (node (ref "U$90") (pin "3") (pinfunction "DI_3") (pintype "bidirectional"))
    )
    (net (code "98") (name "Net-(U$90-DO)") (class "Default")
      (node (ref "U$90") (pin "1") (pinfunction "DO_1") (pintype "bidirectional"))
      (node (ref "U$91") (pin "3") (pinfunction "DI_3") (pintype "bidirectional"))
    )
    (net (code "99") (name "Net-(U$91-DO)") (class "Default")
      (node (ref "U$91") (pin "1") (pinfunction "DO_1") (pintype "bidirectional"))
      (node (ref "U$92") (pin "3") (pinfunction "DI_3") (pintype "bidirectional"))
    )
    (net (code "100") (name "Net-(U$92-DO)") (class "Default")
      (node (ref "U$92") (pin "1") (pinfunction "DO_1") (pintype "bidirectional"))
      (node (ref "U$93") (pin "3") (pinfunction "DI_3") (pintype "bidirectional"))
    )
    (net (code "101") (name "Net-(U$93-DO)") (class "Default")
      (node (ref "U$93") (pin "1") (pinfunction "DO_1") (pintype "bidirectional"))
      (node (ref "U$94") (pin "3") (pinfunction "DI_3") (pintype "bidirectional"))
    )
    (net (code "102") (name "Net-(U$94-DO)") (class "Default")
      (node (ref "U$94") (pin "1") (pinfunction "DO_1") (pintype "bidirectional"))
      (node (ref "U$95") (pin "3") (pinfunction "DI_3") (pintype "bidirectional"))
    )
    (net (code "103") (name "Net-(U$95-DO)") (class "Default")
      (node (ref "U$95") (pin "1") (pinfunction "DO_1") (pintype "bidirectional"))
      (node (ref "U$96") (pin "3") (pinfunction "DI_3") (pintype "bidirectional"))
    )
    (net (code "104") (name "Net-(U$97-DO)") (class "Default")
      (node (ref "U$97") (pin "1") (pinfunction "DO_1") (pintype "bidirectional"))
      (node (ref "U$98") (pin "3") (pinfunction "DI_3") (pintype "bidirectional"))
    )
    (net (code "105") (name "Net-(U$98-DO)") (class "Default")
      (node (ref "U$98") (pin "1") (pinfunction "DO_1") (pintype "bidirectional"))
      (node (ref "U$99") (pin "3") (pinfunction "DI_3") (pintype "bidirectional"))
    )
    (net (code "106") (name "Net-(U$100-DI)") (class "Default")
      (node (ref "U$100") (pin "3") (pinfunction "DI_3") (pintype "bidirectional"))
      (node (ref "U$99") (pin "1") (pinfunction "DO_1") (pintype "bidirectional"))
    )
    (net (code "107") (name "Net-(U$100-DO)") (class "Default")
      (node (ref "U$100") (pin "1") (pinfunction "DO_1") (pintype "bidirectional"))
      (node (ref "U$101") (pin "3") (pinfunction "DI_3") (pintype "bidirectional"))
    )
    (net (code "108") (name "Net-(U$101-DO)") (class "Default")
      (node (ref "U$101") (pin "1") (pinfunction "DO_1") (pintype "bidirectional"))
      (node (ref "U$102") (pin "3") (pinfunction "DI_3") (pintype "bidirectional"))
    )
    (net (code "109") (name "Net-(U$102-DO)") (class "Default")
      (node (ref "U$102") (pin "1") (pinfunction "DO_1") (pintype "bidirectional"))
      (node (ref "U$103") (pin "3") (pinfunction "DI_3") (pintype "bidirectional"))
    )
    (net (code "110") (name "Net-(U$103-DO)") (class "Default")
      (node (ref "U$103") (pin "1") (pinfunction "DO_1") (pintype "bidirectional"))
      (node (ref "U$104") (pin "3") (pinfunction "DI_3") (pintype "bidirectional"))
    )
    (net (code "111") (name "Net-(U$104-DO)") (class "Default")
      (node (ref "U$104") (pin "1") (pinfunction "DO_1") (pintype "bidirectional"))
      (node (ref "U$105") (pin "3") (pinfunction "DI_3") (pintype "bidirectional"))
    )
    (net (code "112") (name "Net-(U$105-DO)") (class "Default")
      (node (ref "U$105") (pin "1") (pinfunction "DO_1") (pintype "bidirectional"))
      (node (ref "U$106") (pin "3") (pinfunction "DI_3") (pintype "bidirectional"))
    )
    (net (code "113") (name "Net-(U$106-DO)") (class "Default")
      (node (ref "U$106") (pin "1") (pinfunction "DO_1") (pintype "bidirectional"))
      (node (ref "U$107") (pin "3") (pinfunction "DI_3") (pintype "bidirectional"))
    )
    (net (code "114") (name "Net-(U$107-DO)") (class "Default")
      (node (ref "U$107") (pin "1") (pinfunction "DO_1") (pintype "bidirectional"))
      (node (ref "U$108") (pin "3") (pinfunction "DI_3") (pintype "bidirectional"))
    )
    (net (code "115") (name "Net-(U$108-DO)") (class "Default")
      (node (ref "U$108") (pin "1") (pinfunction "DO_1") (pintype "bidirectional"))
      (node (ref "U$109") (pin "3") (pinfunction "DI_3") (pintype "bidirectional"))
    )
    (net (code "116") (name "Net-(U$109-DO)") (class "Default")
      (node (ref "U$109") (pin "1") (pinfunction "DO_1") (pintype "bidirectional"))
      (node (ref "U$110") (pin "3") (pinfunction "DI_3") (pintype "bidirectional"))
    )
    (net (code "117") (name "Net-(U$110-DO)") (class "Default")
      (node (ref "U$110") (pin "1") (pinfunction "DO_1") (pintype "bidirectional"))
      (node (ref "U$111") (pin "3") (pinfunction "DI_3") (pintype "bidirectional"))
    )
    (net (code "118") (name "Net-(U$111-DO)") (class "Default")
      (node (ref "U$111") (pin "1") (pinfunction "DO_1") (pintype "bidirectional"))
      (node (ref "U$112") (pin "3") (pinfunction "DI_3") (pintype "bidirectional"))
    )
    (net (code "119") (name "Net-(U$112-DO)") (class "Default")
      (node (ref "U$112") (pin "1") (pinfunction "DO_1") (pintype "bidirectional"))
      (node (ref "U$113") (pin "3") (pinfunction "DI_3") (pintype "bidirectional"))
    )
    (net (code "120") (name "Net-(U$113-DO)") (class "Default")
      (node (ref "U$113") (pin "1") (pinfunction "DO_1") (pintype "bidirectional"))
      (node (ref "U$114") (pin "3") (pinfunction "DI_3") (pintype "bidirectional"))
    )
    (net (code "121") (name "Net-(U$114-DO)") (class "Default")
      (node (ref "U$114") (pin "1") (pinfunction "DO_1") (pintype "bidirectional"))
      (node (ref "U$115") (pin "3") (pinfunction "DI_3") (pintype "bidirectional"))
    )
    (net (code "122") (name "Net-(U$115-DO)") (class "Default")
      (node (ref "U$115") (pin "1") (pinfunction "DO_1") (pintype "bidirectional"))
      (node (ref "U$116") (pin "3") (pinfunction "DI_3") (pintype "bidirectional"))
    )
    (net (code "123") (name "Net-(U$116-DO)") (class "Default")
      (node (ref "U$116") (pin "1") (pinfunction "DO_1") (pintype "bidirectional"))
      (node (ref "U$117") (pin "3") (pinfunction "DI_3") (pintype "bidirectional"))
    )
    (net (code "124") (name "Net-(U$117-DO)") (class "Default")
      (node (ref "U$117") (pin "1") (pinfunction "DO_1") (pintype "bidirectional"))
      (node (ref "U$118") (pin "3") (pinfunction "DI_3") (pintype "bidirectional"))
    )
    (net (code "125") (name "Net-(U$118-DO)") (class "Default")
      (node (ref "U$118") (pin "1") (pinfunction "DO_1") (pintype "bidirectional"))
      (node (ref "U$119") (pin "3") (pinfunction "DI_3") (pintype "bidirectional"))
    )
    (net (code "126") (name "Net-(U$119-DO)") (class "Default")
      (node (ref "U$119") (pin "1") (pinfunction "DO_1") (pintype "bidirectional"))
      (node (ref "U$120") (pin "3") (pinfunction "DI_3") (pintype "bidirectional"))
    )
    (net (code "127") (name "Net-(U$120-DO)") (class "Default")
      (node (ref "U$120") (pin "1") (pinfunction "DO_1") (pintype "bidirectional"))
      (node (ref "U$121") (pin "3") (pinfunction "DI_3") (pintype "bidirectional"))
    )
    (net (code "128") (name "Net-(U$121-DO)") (class "Default")
      (node (ref "U$121") (pin "1") (pinfunction "DO_1") (pintype "bidirectional"))
      (node (ref "U$122") (pin "3") (pinfunction "DI_3") (pintype "bidirectional"))
    )
    (net (code "129") (name "Net-(U$122-DO)") (class "Default")
      (node (ref "U$122") (pin "1") (pinfunction "DO_1") (pintype "bidirectional"))
      (node (ref "U$123") (pin "3") (pinfunction "DI_3") (pintype "bidirectional"))
    )
    (net (code "130") (name "Net-(U$123-DO)") (class "Default")
      (node (ref "U$123") (pin "1") (pinfunction "DO_1") (pintype "bidirectional"))
      (node (ref "U$124") (pin "3") (pinfunction "DI_3") (pintype "bidirectional"))
    )
    (net (code "131") (name "Net-(U$124-DO)") (class "Default")
      (node (ref "U$124") (pin "1") (pinfunction "DO_1") (pintype "bidirectional"))
      (node (ref "U$125") (pin "3") (pinfunction "DI_3") (pintype "bidirectional"))
    )
    (net (code "132") (name "Net-(U$125-DO)") (class "Default")
      (node (ref "U$125") (pin "1") (pinfunction "DO_1") (pintype "bidirectional"))
      (node (ref "U$126") (pin "3") (pinfunction "DI_3") (pintype "bidirectional"))
    )
    (net (code "133") (name "Net-(U$126-DO)") (class "Default")
      (node (ref "U$126") (pin "1") (pinfunction "DO_1") (pintype "bidirectional"))
      (node (ref "U$127") (pin "3") (pinfunction "DI_3") (pintype "bidirectional"))
    )
    (net (code "134") (name "Net-(U$127-DO)") (class "Default")
      (node (ref "U$127") (pin "1") (pinfunction "DO_1") (pintype "bidirectional"))
      (node (ref "U$128") (pin "3") (pinfunction "DI_3") (pintype "bidirectional"))
    )
    (net (code "135") (name "Net-(U$129-DO)") (class "Default")
      (node (ref "U$129") (pin "1") (pinfunction "DO_1") (pintype "bidirectional"))
      (node (ref "U$130") (pin "3") (pinfunction "DI_3") (pintype "bidirectional"))
    )
    (net (code "136") (name "Net-(U$130-DO)") (class "Default")
      (node (ref "U$130") (pin "1") (pinfunction "DO_1") (pintype "bidirectional"))
      (node (ref "U$131") (pin "3") (pinfunction "DI_3") (pintype "bidirectional"))
    )
    (net (code "137") (name "Net-(U$131-DO)") (class "Default")
      (node (ref "U$131") (pin "1") (pinfunction "DO_1") (pintype "bidirectional"))
      (node (ref "U$132") (pin "3") (pinfunction "DI_3") (pintype "bidirectional"))
    )
    (net (code "138") (name "Net-(U$132-DO)") (class "Default")
      (node (ref "U$132") (pin "1") (pinfunction "DO_1") (pintype "bidirectional"))
      (node (ref "U$133") (pin "3") (pinfunction "DI_3") (pintype "bidirectional"))
    )
    (net (code "139") (name "Net-(U$133-DO)") (class "Default")
      (node (ref "U$133") (pin "1") (pinfunction "DO_1") (pintype "bidirectional"))
      (node (ref "U$134") (pin "3") (pinfunction "DI_3") (pintype "bidirectional"))
    )
    (net (code "140") (name "Net-(U$134-DO)") (class "Default")
      (node (ref "U$134") (pin "1") (pinfunction "DO_1") (pintype "bidirectional"))
      (node (ref "U$135") (pin "3") (pinfunction "DI_3") (pintype "bidirectional"))
    )
    (net (code "141") (name "Net-(U$135-DO)") (class "Default")
      (node (ref "U$135") (pin "1") (pinfunction "DO_1") (pintype "bidirectional"))
      (node (ref "U$136") (pin "3") (pinfunction "DI_3") (pintype "bidirectional"))
    )
    (net (code "142") (name "Net-(U$136-DO)") (class "Default")
      (node (ref "U$136") (pin "1") (pinfunction "DO_1") (pintype "bidirectional"))
      (node (ref "U$137") (pin "3") (pinfunction "DI_3") (pintype "bidirectional"))
    )
    (net (code "143") (name "Net-(U$137-DO)") (class "Default")
      (node (ref "U$137") (pin "1") (pinfunction "DO_1") (pintype "bidirectional"))
      (node (ref "U$138") (pin "3") (pinfunction "DI_3") (pintype "bidirectional"))
    )
    (net (code "144") (name "Net-(U$138-DO)") (class "Default")
      (node (ref "U$138") (pin "1") (pinfunction "DO_1") (pintype "bidirectional"))
      (node (ref "U$139") (pin "3") (pinfunction "DI_3") (pintype "bidirectional"))
    )
    (net (code "145") (name "Net-(U$139-DO)") (class "Default")
      (node (ref "U$139") (pin "1") (pinfunction "DO_1") (pintype "bidirectional"))
      (node (ref "U$140") (pin "3") (pinfunction "DI_3") (pintype "bidirectional"))
    )
    (net (code "146") (name "Net-(U$140-DO)") (class "Default")
      (node (ref "U$140") (pin "1") (pinfunction "DO_1") (pintype "bidirectional"))
      (node (ref "U$141") (pin "3") (pinfunction "DI_3") (pintype "bidirectional"))
    )
    (net (code "147") (name "Net-(U$141-DO)") (class "Default")
      (node (ref "U$141") (pin "1") (pinfunction "DO_1") (pintype "bidirectional"))
      (node (ref "U$142") (pin "3") (pinfunction "DI_3") (pintype "bidirectional"))
    )
    (net (code "148") (name "Net-(U$142-DO)") (class "Default")
      (node (ref "U$142") (pin "1") (pinfunction "DO_1") (pintype "bidirectional"))
      (node (ref "U$143") (pin "3") (pinfunction "DI_3") (pintype "bidirectional"))
    )
    (net (code "149") (name "Net-(U$143-DO)") (class "Default")
      (node (ref "U$143") (pin "1") (pinfunction "DO_1") (pintype "bidirectional"))
      (node (ref "U$144") (pin "3") (pinfunction "DI_3") (pintype "bidirectional"))
    )
    (net (code "150") (name "Net-(U$144-DO)") (class "Default")
      (node (ref "U$144") (pin "1") (pinfunction "DO_1") (pintype "bidirectional"))
      (node (ref "U$145") (pin "3") (pinfunction "DI_3") (pintype "bidirectional"))
    )
    (net (code "151") (name "Net-(U$145-DO)") (class "Default")
      (node (ref "U$145") (pin "1") (pinfunction "DO_1") (pintype "bidirectional"))
      (node (ref "U$146") (pin "3") (pinfunction "DI_3") (pintype "bidirectional"))
    )
    (net (code "152") (name "Net-(U$146-DO)") (class "Default")
      (node (ref "U$146") (pin "1") (pinfunction "DO_1") (pintype "bidirectional"))
      (node (ref "U$147") (pin "3") (pinfunction "DI_3") (pintype "bidirectional"))
    )
    (net (code "153") (name "Net-(U$147-DO)") (class "Default")
      (node (ref "U$147") (pin "1") (pinfunction "DO_1") (pintype "bidirectional"))
      (node (ref "U$148") (pin "3") (pinfunction "DI_3") (pintype "bidirectional"))
    )
    (net (code "154") (name "Net-(U$148-DO)") (class "Default")
      (node (ref "U$148") (pin "1") (pinfunction "DO_1") (pintype "bidirectional"))
      (node (ref "U$149") (pin "3") (pinfunction "DI_3") (pintype "bidirectional"))
    )
    (net (code "155") (name "Net-(U$149-DO)") (class "Default")
      (node (ref "U$149") (pin "1") (pinfunction "DO_1") (pintype "bidirectional"))
      (node (ref "U$150") (pin "3") (pinfunction "DI_3") (pintype "bidirectional"))
    )
    (net (code "156") (name "Net-(U$150-DO)") (class "Default")
      (node (ref "U$150") (pin "1") (pinfunction "DO_1") (pintype "bidirectional"))
      (node (ref "U$151") (pin "3") (pinfunction "DI_3") (pintype "bidirectional"))
    )
    (net (code "157") (name "Net-(U$151-DO)") (class "Default")
      (node (ref "U$151") (pin "1") (pinfunction "DO_1") (pintype "bidirectional"))
      (node (ref "U$152") (pin "3") (pinfunction "DI_3") (pintype "bidirectional"))
    )
    (net (code "158") (name "Net-(U$152-DO)") (class "Default")
      (node (ref "U$152") (pin "1") (pinfunction "DO_1") (pintype "bidirectional"))
      (node (ref "U$153") (pin "3") (pinfunction "DI_3") (pintype "bidirectional"))
    )
    (net (code "159") (name "Net-(U$153-DO)") (class "Default")
      (node (ref "U$153") (pin "1") (pinfunction "DO_1") (pintype "bidirectional"))
      (node (ref "U$154") (pin "3") (pinfunction "DI_3") (pintype "bidirectional"))
    )
    (net (code "160") (name "Net-(U$154-DO)") (class "Default")
      (node (ref "U$154") (pin "1") (pinfunction "DO_1") (pintype "bidirectional"))
      (node (ref "U$155") (pin "3") (pinfunction "DI_3") (pintype "bidirectional"))
    )
    (net (code "161") (name "Net-(U$155-DO)") (class "Default")
      (node (ref "U$155") (pin "1") (pinfunction "DO_1") (pintype "bidirectional"))
      (node (ref "U$156") (pin "3") (pinfunction "DI_3") (pintype "bidirectional"))
    )
    (net (code "162") (name "Net-(U$156-DO)") (class "Default")
      (node (ref "U$156") (pin "1") (pinfunction "DO_1") (pintype "bidirectional"))
      (node (ref "U$157") (pin "3") (pinfunction "DI_3") (pintype "bidirectional"))
    )
    (net (code "163") (name "Net-(U$157-DO)") (class "Default")
      (node (ref "U$157") (pin "1") (pinfunction "DO_1") (pintype "bidirectional"))
      (node (ref "U$158") (pin "3") (pinfunction "DI_3") (pintype "bidirectional"))
    )
    (net (code "164") (name "Net-(U$158-DO)") (class "Default")
      (node (ref "U$158") (pin "1") (pinfunction "DO_1") (pintype "bidirectional"))
      (node (ref "U$159") (pin "3") (pinfunction "DI_3") (pintype "bidirectional"))
    )
    (net (code "165") (name "Net-(U$159-DO)") (class "Default")
      (node (ref "U$159") (pin "1") (pinfunction "DO_1") (pintype "bidirectional"))
      (node (ref "U$160") (pin "3") (pinfunction "DI_3") (pintype "bidirectional"))
    )
    (net (code "166") (name "Net-(U$161-DO)") (class "Default")
      (node (ref "U$161") (pin "1") (pinfunction "DO_1") (pintype "bidirectional"))
      (node (ref "U$162") (pin "3") (pinfunction "DI_3") (pintype "bidirectional"))
    )
    (net (code "167") (name "Net-(U$162-DO)") (class "Default")
      (node (ref "U$162") (pin "1") (pinfunction "DO_1") (pintype "bidirectional"))
      (node (ref "U$163") (pin "3") (pinfunction "DI_3") (pintype "bidirectional"))
    )
    (net (code "168") (name "Net-(U$163-DO)") (class "Default")
      (node (ref "U$163") (pin "1") (pinfunction "DO_1") (pintype "bidirectional"))
      (node (ref "U$164") (pin "3") (pinfunction "DI_3") (pintype "bidirectional"))
    )
    (net (code "169") (name "Net-(U$164-DO)") (class "Default")
      (node (ref "U$164") (pin "1") (pinfunction "DO_1") (pintype "bidirectional"))
      (node (ref "U$165") (pin "3") (pinfunction "DI_3") (pintype "bidirectional"))
    )
    (net (code "170") (name "Net-(U$165-DO)") (class "Default")
      (node (ref "U$165") (pin "1") (pinfunction "DO_1") (pintype "bidirectional"))
      (node (ref "U$166") (pin "3") (pinfunction "DI_3") (pintype "bidirectional"))
    )
    (net (code "171") (name "Net-(U$166-DO)") (class "Default")
      (node (ref "U$166") (pin "1") (pinfunction "DO_1") (pintype "bidirectional"))
      (node (ref "U$167") (pin "3") (pinfunction "DI_3") (pintype "bidirectional"))
    )
    (net (code "172") (name "Net-(U$167-DO)") (class "Default")
      (node (ref "U$167") (pin "1") (pinfunction "DO_1") (pintype "bidirectional"))
      (node (ref "U$168") (pin "3") (pinfunction "DI_3") (pintype "bidirectional"))
    )
    (net (code "173") (name "Net-(U$168-DO)") (class "Default")
      (node (ref "U$168") (pin "1") (pinfunction "DO_1") (pintype "bidirectional"))
      (node (ref "U$169") (pin "3") (pinfunction "DI_3") (pintype "bidirectional"))
    )
    (net (code "174") (name "Net-(U$169-DO)") (class "Default")
      (node (ref "U$169") (pin "1") (pinfunction "DO_1") (pintype "bidirectional"))
      (node (ref "U$170") (pin "3") (pinfunction "DI_3") (pintype "bidirectional"))
    )
    (net (code "175") (name "Net-(U$170-DO)") (class "Default")
      (node (ref "U$170") (pin "1") (pinfunction "DO_1") (pintype "bidirectional"))
      (node (ref "U$171") (pin "3") (pinfunction "DI_3") (pintype "bidirectional"))
    )
    (net (code "176") (name "Net-(U$171-DO)") (class "Default")
      (node (ref "U$171") (pin "1") (pinfunction "DO_1") (pintype "bidirectional"))
      (node (ref "U$172") (pin "3") (pinfunction "DI_3") (pintype "bidirectional"))
    )
    (net (code "177") (name "Net-(U$172-DO)") (class "Default")
      (node (ref "U$172") (pin "1") (pinfunction "DO_1") (pintype "bidirectional"))
      (node (ref "U$173") (pin "3") (pinfunction "DI_3") (pintype "bidirectional"))
    )
    (net (code "178") (name "Net-(U$173-DO)") (class "Default")
      (node (ref "U$173") (pin "1") (pinfunction "DO_1") (pintype "bidirectional"))
      (node (ref "U$174") (pin "3") (pinfunction "DI_3") (pintype "bidirectional"))
    )
    (net (code "179") (name "Net-(U$174-DO)") (class "Default")
      (node (ref "U$174") (pin "1") (pinfunction "DO_1") (pintype "bidirectional"))
      (node (ref "U$175") (pin "3") (pinfunction "DI_3") (pintype "bidirectional"))
    )
    (net (code "180") (name "Net-(U$175-DO)") (class "Default")
      (node (ref "U$175") (pin "1") (pinfunction "DO_1") (pintype "bidirectional"))
      (node (ref "U$176") (pin "3") (pinfunction "DI_3") (pintype "bidirectional"))
    )
    (net (code "181") (name "Net-(U$176-DO)") (class "Default")
      (node (ref "U$176") (pin "1") (pinfunction "DO_1") (pintype "bidirectional"))
      (node (ref "U$177") (pin "3") (pinfunction "DI_3") (pintype "bidirectional"))
    )
    (net (code "182") (name "Net-(U$177-DO)") (class "Default")
      (node (ref "U$177") (pin "1") (pinfunction "DO_1") (pintype "bidirectional"))
      (node (ref "U$178") (pin "3") (pinfunction "DI_3") (pintype "bidirectional"))
    )
    (net (code "183") (name "Net-(U$178-DO)") (class "Default")
      (node (ref "U$178") (pin "1") (pinfunction "DO_1") (pintype "bidirectional"))
      (node (ref "U$179") (pin "3") (pinfunction "DI_3") (pintype "bidirectional"))
    )
    (net (code "184") (name "Net-(U$179-DO)") (class "Default")
      (node (ref "U$179") (pin "1") (pinfunction "DO_1") (pintype "bidirectional"))
      (node (ref "U$180") (pin "3") (pinfunction "DI_3") (pintype "bidirectional"))
    )
    (net (code "185") (name "Net-(U$180-DO)") (class "Default")
      (node (ref "U$180") (pin "1") (pinfunction "DO_1") (pintype "bidirectional"))
      (node (ref "U$181") (pin "3") (pinfunction "DI_3") (pintype "bidirectional"))
    )
    (net (code "186") (name "Net-(U$181-DO)") (class "Default")
      (node (ref "U$181") (pin "1") (pinfunction "DO_1") (pintype "bidirectional"))
      (node (ref "U$182") (pin "3") (pinfunction "DI_3") (pintype "bidirectional"))
    )
    (net (code "187") (name "Net-(U$182-DO)") (class "Default")
      (node (ref "U$182") (pin "1") (pinfunction "DO_1") (pintype "bidirectional"))
      (node (ref "U$183") (pin "3") (pinfunction "DI_3") (pintype "bidirectional"))
    )
    (net (code "188") (name "Net-(U$183-DO)") (class "Default")
      (node (ref "U$183") (pin "1") (pinfunction "DO_1") (pintype "bidirectional"))
      (node (ref "U$184") (pin "3") (pinfunction "DI_3") (pintype "bidirectional"))
    )
    (net (code "189") (name "Net-(U$184-DO)") (class "Default")
      (node (ref "U$184") (pin "1") (pinfunction "DO_1") (pintype "bidirectional"))
      (node (ref "U$185") (pin "3") (pinfunction "DI_3") (pintype "bidirectional"))
    )
    (net (code "190") (name "Net-(U$185-DO)") (class "Default")
      (node (ref "U$185") (pin "1") (pinfunction "DO_1") (pintype "bidirectional"))
      (node (ref "U$186") (pin "3") (pinfunction "DI_3") (pintype "bidirectional"))
    )
    (net (code "191") (name "Net-(U$186-DO)") (class "Default")
      (node (ref "U$186") (pin "1") (pinfunction "DO_1") (pintype "bidirectional"))
      (node (ref "U$187") (pin "3") (pinfunction "DI_3") (pintype "bidirectional"))
    )
    (net (code "192") (name "Net-(U$187-DO)") (class "Default")
      (node (ref "U$187") (pin "1") (pinfunction "DO_1") (pintype "bidirectional"))
      (node (ref "U$188") (pin "3") (pinfunction "DI_3") (pintype "bidirectional"))
    )
    (net (code "193") (name "Net-(U$188-DO)") (class "Default")
      (node (ref "U$188") (pin "1") (pinfunction "DO_1") (pintype "bidirectional"))
      (node (ref "U$189") (pin "3") (pinfunction "DI_3") (pintype "bidirectional"))
    )
    (net (code "194") (name "Net-(U$189-DO)") (class "Default")
      (node (ref "U$189") (pin "1") (pinfunction "DO_1") (pintype "bidirectional"))
      (node (ref "U$190") (pin "3") (pinfunction "DI_3") (pintype "bidirectional"))
    )
    (net (code "195") (name "Net-(U$190-DO)") (class "Default")
      (node (ref "U$190") (pin "1") (pinfunction "DO_1") (pintype "bidirectional"))
      (node (ref "U$191") (pin "3") (pinfunction "DI_3") (pintype "bidirectional"))
    )
    (net (code "196") (name "Net-(U$191-DO)") (class "Default")
      (node (ref "U$191") (pin "1") (pinfunction "DO_1") (pintype "bidirectional"))
      (node (ref "U$192") (pin "3") (pinfunction "DI_3") (pintype "bidirectional"))
    )
    (net (code "197") (name "Net-(U$193-DO)") (class "Default")
      (node (ref "U$193") (pin "1") (pinfunction "DO_1") (pintype "bidirectional"))
      (node (ref "U$194") (pin "3") (pinfunction "DI_3") (pintype "bidirectional"))
    )
    (net (code "198") (name "Net-(U$194-DO)") (class "Default")
      (node (ref "U$194") (pin "1") (pinfunction "DO_1") (pintype "bidirectional"))
      (node (ref "U$195") (pin "3") (pinfunction "DI_3") (pintype "bidirectional"))
    )
    (net (code "199") (name "Net-(U$195-DO)") (class "Default")
      (node (ref "U$195") (pin "1") (pinfunction "DO_1") (pintype "bidirectional"))
      (node (ref "U$196") (pin "3") (pinfunction "DI_3") (pintype "bidirectional"))
    )
    (net (code "200") (name "Net-(U$196-DO)") (class "Default")
      (node (ref "U$196") (pin "1") (pinfunction "DO_1") (pintype "bidirectional"))
      (node (ref "U$197") (pin "3") (pinfunction "DI_3") (pintype "bidirectional"))
    )
    (net (code "201") (name "Net-(U$197-DO)") (class "Default")
      (node (ref "U$197") (pin "1") (pinfunction "DO_1") (pintype "bidirectional"))
      (node (ref "U$198") (pin "3") (pinfunction "DI_3") (pintype "bidirectional"))
    )
    (net (code "202") (name "Net-(U$198-DO)") (class "Default")
      (node (ref "U$198") (pin "1") (pinfunction "DO_1") (pintype "bidirectional"))
      (node (ref "U$199") (pin "3") (pinfunction "DI_3") (pintype "bidirectional"))
    )
    (net (code "203") (name "Net-(U$199-DO)") (class "Default")
      (node (ref "U$199") (pin "1") (pinfunction "DO_1") (pintype "bidirectional"))
      (node (ref "U$200") (pin "3") (pinfunction "DI_3") (pintype "bidirectional"))
    )
    (net (code "204") (name "Net-(U$200-DO)") (class "Default")
      (node (ref "U$200") (pin "1") (pinfunction "DO_1") (pintype "bidirectional"))
      (node (ref "U$201") (pin "3") (pinfunction "DI_3") (pintype "bidirectional"))
    )
    (net (code "205") (name "Net-(U$201-DO)") (class "Default")
      (node (ref "U$201") (pin "1") (pinfunction "DO_1") (pintype "bidirectional"))
      (node (ref "U$202") (pin "3") (pinfunction "DI_3") (pintype "bidirectional"))
    )
    (net (code "206") (name "Net-(U$202-DO)") (class "Default")
      (node (ref "U$202") (pin "1") (pinfunction "DO_1") (pintype "bidirectional"))
      (node (ref "U$203") (pin "3") (pinfunction "DI_3") (pintype "bidirectional"))
    )
    (net (code "207") (name "Net-(U$203-DO)") (class "Default")
      (node (ref "U$203") (pin "1") (pinfunction "DO_1") (pintype "bidirectional"))
      (node (ref "U$204") (pin "3") (pinfunction "DI_3") (pintype "bidirectional"))
    )
    (net (code "208") (name "Net-(U$204-DO)") (class "Default")
      (node (ref "U$204") (pin "1") (pinfunction "DO_1") (pintype "bidirectional"))
      (node (ref "U$205") (pin "3") (pinfunction "DI_3") (pintype "bidirectional"))
    )
    (net (code "209") (name "Net-(U$205-DO)") (class "Default")
      (node (ref "U$205") (pin "1") (pinfunction "DO_1") (pintype "bidirectional"))
      (node (ref "U$206") (pin "3") (pinfunction "DI_3") (pintype "bidirectional"))
    )
    (net (code "210") (name "Net-(U$206-DO)") (class "Default")
      (node (ref "U$206") (pin "1") (pinfunction "DO_1") (pintype "bidirectional"))
      (node (ref "U$207") (pin "3") (pinfunction "DI_3") (pintype "bidirectional"))
    )
    (net (code "211") (name "Net-(U$207-DO)") (class "Default")
      (node (ref "U$207") (pin "1") (pinfunction "DO_1") (pintype "bidirectional"))
      (node (ref "U$208") (pin "3") (pinfunction "DI_3") (pintype "bidirectional"))
    )
    (net (code "212") (name "Net-(U$208-DO)") (class "Default")
      (node (ref "U$208") (pin "1") (pinfunction "DO_1") (pintype "bidirectional"))
      (node (ref "U$209") (pin "3") (pinfunction "DI_3") (pintype "bidirectional"))
    )
    (net (code "213") (name "Net-(U$209-DO)") (class "Default")
      (node (ref "U$209") (pin "1") (pinfunction "DO_1") (pintype "bidirectional"))
      (node (ref "U$210") (pin "3") (pinfunction "DI_3") (pintype "bidirectional"))
    )
    (net (code "214") (name "Net-(U$210-DO)") (class "Default")
      (node (ref "U$210") (pin "1") (pinfunction "DO_1") (pintype "bidirectional"))
      (node (ref "U$211") (pin "3") (pinfunction "DI_3") (pintype "bidirectional"))
    )
    (net (code "215") (name "Net-(U$211-DO)") (class "Default")
      (node (ref "U$211") (pin "1") (pinfunction "DO_1") (pintype "bidirectional"))
      (node (ref "U$212") (pin "3") (pinfunction "DI_3") (pintype "bidirectional"))
    )
    (net (code "216") (name "Net-(U$212-DO)") (class "Default")
      (node (ref "U$212") (pin "1") (pinfunction "DO_1") (pintype "bidirectional"))
      (node (ref "U$213") (pin "3") (pinfunction "DI_3") (pintype "bidirectional"))
    )
    (net (code "217") (name "Net-(U$213-DO)") (class "Default")
      (node (ref "U$213") (pin "1") (pinfunction "DO_1") (pintype "bidirectional"))
      (node (ref "U$214") (pin "3") (pinfunction "DI_3") (pintype "bidirectional"))
    )
    (net (code "218") (name "Net-(U$214-DO)") (class "Default")
      (node (ref "U$214") (pin "1") (pinfunction "DO_1") (pintype "bidirectional"))
      (node (ref "U$215") (pin "3") (pinfunction "DI_3") (pintype "bidirectional"))
    )
    (net (code "219") (name "Net-(U$215-DO)") (class "Default")
      (node (ref "U$215") (pin "1") (pinfunction "DO_1") (pintype "bidirectional"))
      (node (ref "U$216") (pin "3") (pinfunction "DI_3") (pintype "bidirectional"))
    )
    (net (code "220") (name "Net-(U$216-DO)") (class "Default")
      (node (ref "U$216") (pin "1") (pinfunction "DO_1") (pintype "bidirectional"))
      (node (ref "U$217") (pin "3") (pinfunction "DI_3") (pintype "bidirectional"))
    )
    (net (code "221") (name "Net-(U$217-DO)") (class "Default")
      (node (ref "U$217") (pin "1") (pinfunction "DO_1") (pintype "bidirectional"))
      (node (ref "U$218") (pin "3") (pinfunction "DI_3") (pintype "bidirectional"))
    )
    (net (code "222") (name "Net-(U$218-DO)") (class "Default")
      (node (ref "U$218") (pin "1") (pinfunction "DO_1") (pintype "bidirectional"))
      (node (ref "U$219") (pin "3") (pinfunction "DI_3") (pintype "bidirectional"))
    )
    (net (code "223") (name "Net-(U$219-DO)") (class "Default")
      (node (ref "U$219") (pin "1") (pinfunction "DO_1") (pintype "bidirectional"))
      (node (ref "U$220") (pin "3") (pinfunction "DI_3") (pintype "bidirectional"))
    )
    (net (code "224") (name "Net-(U$220-DO)") (class "Default")
      (node (ref "U$220") (pin "1") (pinfunction "DO_1") (pintype "bidirectional"))
      (node (ref "U$221") (pin "3") (pinfunction "DI_3") (pintype "bidirectional"))
    )
    (net (code "225") (name "Net-(U$221-DO)") (class "Default")
      (node (ref "U$221") (pin "1") (pinfunction "DO_1") (pintype "bidirectional"))
      (node (ref "U$222") (pin "3") (pinfunction "DI_3") (pintype "bidirectional"))
    )
    (net (code "226") (name "Net-(U$222-DO)") (class "Default")
      (node (ref "U$222") (pin "1") (pinfunction "DO_1") (pintype "bidirectional"))
      (node (ref "U$223") (pin "3") (pinfunction "DI_3") (pintype "bidirectional"))
    )
    (net (code "227") (name "Net-(U$223-DO)") (class "Default")
      (node (ref "U$223") (pin "1") (pinfunction "DO_1") (pintype "bidirectional"))
      (node (ref "U$224") (pin "3") (pinfunction "DI_3") (pintype "bidirectional"))
    )
    (net (code "228") (name "Net-(U$225-DO)") (class "Default")
      (node (ref "U$225") (pin "1") (pinfunction "DO_1") (pintype "bidirectional"))
      (node (ref "U$226") (pin "3") (pinfunction "DI_3") (pintype "bidirectional"))
    )
    (net (code "229") (name "Net-(U$226-DO)") (class "Default")
      (node (ref "U$226") (pin "1") (pinfunction "DO_1") (pintype "bidirectional"))
      (node (ref "U$227") (pin "3") (pinfunction "DI_3") (pintype "bidirectional"))
    )
    (net (code "230") (name "Net-(U$227-DO)") (class "Default")
      (node (ref "U$227") (pin "1") (pinfunction "DO_1") (pintype "bidirectional"))
      (node (ref "U$228") (pin "3") (pinfunction "DI_3") (pintype "bidirectional"))
    )
    (net (code "231") (name "Net-(U$228-DO)") (class "Default")
      (node (ref "U$228") (pin "1") (pinfunction "DO_1") (pintype "bidirectional"))
      (node (ref "U$229") (pin "3") (pinfunction "DI_3") (pintype "bidirectional"))
    )
    (net (code "232") (name "Net-(U$229-DO)") (class "Default")
      (node (ref "U$229") (pin "1") (pinfunction "DO_1") (pintype "bidirectional"))
      (node (ref "U$230") (pin "3") (pinfunction "DI_3") (pintype "bidirectional"))
    )
    (net (code "233") (name "Net-(U$230-DO)") (class "Default")
      (node (ref "U$230") (pin "1") (pinfunction "DO_1") (pintype "bidirectional"))
      (node (ref "U$231") (pin "3") (pinfunction "DI_3") (pintype "bidirectional"))
    )
    (net (code "234") (name "Net-(U$231-DO)") (class "Default")
      (node (ref "U$231") (pin "1") (pinfunction "DO_1") (pintype "bidirectional"))
      (node (ref "U$232") (pin "3") (pinfunction "DI_3") (pintype "bidirectional"))
    )
    (net (code "235") (name "Net-(U$232-DO)") (class "Default")
      (node (ref "U$232") (pin "1") (pinfunction "DO_1") (pintype "bidirectional"))
      (node (ref "U$233") (pin "3") (pinfunction "DI_3") (pintype "bidirectional"))
    )
    (net (code "236") (name "Net-(U$233-DO)") (class "Default")
      (node (ref "U$233") (pin "1") (pinfunction "DO_1") (pintype "bidirectional"))
      (node (ref "U$234") (pin "3") (pinfunction "DI_3") (pintype "bidirectional"))
    )
    (net (code "237") (name "Net-(U$234-DO)") (class "Default")
      (node (ref "U$234") (pin "1") (pinfunction "DO_1") (pintype "bidirectional"))
      (node (ref "U$235") (pin "3") (pinfunction "DI_3") (pintype "bidirectional"))
    )
    (net (code "238") (name "Net-(U$235-DO)") (class "Default")
      (node (ref "U$235") (pin "1") (pinfunction "DO_1") (pintype "bidirectional"))
      (node (ref "U$236") (pin "3") (pinfunction "DI_3") (pintype "bidirectional"))
    )
    (net (code "239") (name "Net-(U$236-DO)") (class "Default")
      (node (ref "U$236") (pin "1") (pinfunction "DO_1") (pintype "bidirectional"))
      (node (ref "U$237") (pin "3") (pinfunction "DI_3") (pintype "bidirectional"))
    )
    (net (code "240") (name "Net-(U$237-DO)") (class "Default")
      (node (ref "U$237") (pin "1") (pinfunction "DO_1") (pintype "bidirectional"))
      (node (ref "U$238") (pin "3") (pinfunction "DI_3") (pintype "bidirectional"))
    )
    (net (code "241") (name "Net-(U$238-DO)") (class "Default")
      (node (ref "U$238") (pin "1") (pinfunction "DO_1") (pintype "bidirectional"))
      (node (ref "U$239") (pin "3") (pinfunction "DI_3") (pintype "bidirectional"))
    )
    (net (code "242") (name "Net-(U$239-DO)") (class "Default")
      (node (ref "U$239") (pin "1") (pinfunction "DO_1") (pintype "bidirectional"))
      (node (ref "U$240") (pin "3") (pinfunction "DI_3") (pintype "bidirectional"))
    )
    (net (code "243") (name "Net-(U$240-DO)") (class "Default")
      (node (ref "U$240") (pin "1") (pinfunction "DO_1") (pintype "bidirectional"))
      (node (ref "U$241") (pin "3") (pinfunction "DI_3") (pintype "bidirectional"))
    )
    (net (code "244") (name "Net-(U$241-DO)") (class "Default")
      (node (ref "U$241") (pin "1") (pinfunction "DO_1") (pintype "bidirectional"))
      (node (ref "U$242") (pin "3") (pinfunction "DI_3") (pintype "bidirectional"))
    )
    (net (code "245") (name "Net-(U$242-DO)") (class "Default")
      (node (ref "U$242") (pin "1") (pinfunction "DO_1") (pintype "bidirectional"))
      (node (ref "U$243") (pin "3") (pinfunction "DI_3") (pintype "bidirectional"))
    )
    (net (code "246") (name "Net-(U$243-DO)") (class "Default")
      (node (ref "U$243") (pin "1") (pinfunction "DO_1") (pintype "bidirectional"))
      (node (ref "U$244") (pin "3") (pinfunction "DI_3") (pintype "bidirectional"))
    )
    (net (code "247") (name "Net-(U$244-DO)") (class "Default")
      (node (ref "U$244") (pin "1") (pinfunction "DO_1") (pintype "bidirectional"))
      (node (ref "U$245") (pin "3") (pinfunction "DI_3") (pintype "bidirectional"))
    )
    (net (code "248") (name "Net-(U$245-DO)") (class "Default")
      (node (ref "U$245") (pin "1") (pinfunction "DO_1") (pintype "bidirectional"))
      (node (ref "U$246") (pin "3") (pinfunction "DI_3") (pintype "bidirectional"))
    )
    (net (code "249") (name "Net-(U$246-DO)") (class "Default")
      (node (ref "U$246") (pin "1") (pinfunction "DO_1") (pintype "bidirectional"))
      (node (ref "U$247") (pin "3") (pinfunction "DI_3") (pintype "bidirectional"))
    )
    (net (code "250") (name "Net-(U$247-DO)") (class "Default")
      (node (ref "U$247") (pin "1") (pinfunction "DO_1") (pintype "bidirectional"))
      (node (ref "U$248") (pin "3") (pinfunction "DI_3") (pintype "bidirectional"))
    )
    (net (code "251") (name "Net-(U$248-DO)") (class "Default")
      (node (ref "U$248") (pin "1") (pinfunction "DO_1") (pintype "bidirectional"))
      (node (ref "U$249") (pin "3") (pinfunction "DI_3") (pintype "bidirectional"))
    )
    (net (code "252") (name "Net-(U$249-DO)") (class "Default")
      (node (ref "U$249") (pin "1") (pinfunction "DO_1") (pintype "bidirectional"))
      (node (ref "U$250") (pin "3") (pinfunction "DI_3") (pintype "bidirectional"))
    )
    (net (code "253") (name "Net-(U$250-DO)") (class "Default")
      (node (ref "U$250") (pin "1") (pinfunction "DO_1") (pintype "bidirectional"))
      (node (ref "U$251") (pin "3") (pinfunction "DI_3") (pintype "bidirectional"))
    )
    (net (code "254") (name "Net-(U$251-DO)") (class "Default")
      (node (ref "U$251") (pin "1") (pinfunction "DO_1") (pintype "bidirectional"))
      (node (ref "U$252") (pin "3") (pinfunction "DI_3") (pintype "bidirectional"))
    )
    (net (code "255") (name "Net-(U$252-DO)") (class "Default")
      (node (ref "U$252") (pin "1") (pinfunction "DO_1") (pintype "bidirectional"))
      (node (ref "U$253") (pin "3") (pinfunction "DI_3") (pintype "bidirectional"))
    )
    (net (code "256") (name "Net-(U$253-DO)") (class "Default")
      (node (ref "U$253") (pin "1") (pinfunction "DO_1") (pintype "bidirectional"))
      (node (ref "U$254") (pin "3") (pinfunction "DI_3") (pintype "bidirectional"))
    )
    (net (code "257") (name "Net-(U$254-DO)") (class "Default")
      (node (ref "U$254") (pin "1") (pinfunction "DO_1") (pintype "bidirectional"))
      (node (ref "U$255") (pin "3") (pinfunction "DI_3") (pintype "bidirectional"))
    )
    (net (code "258") (name "Net-(U$255-DO)") (class "Default")
      (node (ref "U$255") (pin "1") (pinfunction "DO_1") (pintype "bidirectional"))
      (node (ref "U$256") (pin "3") (pinfunction "DI_3") (pintype "bidirectional"))
    )
    (net (code "259") (name "VCC") (class "Default")
      (node (ref "J1") (pin "2") (pinfunction "2_2") (pintype "passive"))
      (node (ref "J2") (pin "1") (pinfunction "1_1") (pintype "passive"))
      (node (ref "U$1") (pin "4") (pinfunction "VDD_4") (pintype "bidirectional"))
      (node (ref "U$10") (pin "4") (pinfunction "VDD_4") (pintype "bidirectional"))
      (node (ref "U$100") (pin "4") (pinfunction "VDD_4") (pintype "bidirectional"))
      (node (ref "U$101") (pin "4") (pinfunction "VDD_4") (pintype "bidirectional"))
      (node (ref "U$102") (pin "4") (pinfunction "VDD_4") (pintype "bidirectional"))
      (node (ref "U$103") (pin "4") (pinfunction "VDD_4") (pintype "bidirectional"))
      (node (ref "U$104") (pin "4") (pinfunction "VDD_4") (pintype "bidirectional"))
      (node (ref "U$105") (pin "4") (pinfunction "VDD_4") (pintype "bidirectional"))
      (node (ref "U$106") (pin "4") (pinfunction "VDD_4") (pintype "bidirectional"))
      (node (ref "U$107") (pin "4") (pinfunction "VDD_4") (pintype "bidirectional"))
      (node (ref "U$108") (pin "4") (pinfunction "VDD_4") (pintype "bidirectional"))
      (node (ref "U$109") (pin "4") (pinfunction "VDD_4") (pintype "bidirectional"))
      (node (ref "U$11") (pin "4") (pinfunction "VDD_4") (pintype "bidirectional"))
      (node (ref "U$110") (pin "4") (pinfunction "VDD_4") (pintype "bidirectional"))
      (node (ref "U$111") (pin "4") (pinfunction "VDD_4") (pintype "bidirectional"))
      (node (ref "U$112") (pin "4") (pinfunction "VDD_4") (pintype "bidirectional"))
      (node (ref "U$113") (pin "4") (pinfunction "VDD_4") (pintype "bidirectional"))
      (node (ref "U$114") (pin "4") (pinfunction "VDD_4") (pintype "bidirectional"))
      (node (ref "U$115") (pin "4") (pinfunction "VDD_4") (pintype "bidirectional"))
      (node (ref "U$116") (pin "4") (pinfunction "VDD_4") (pintype "bidirectional"))
      (node (ref "U$117") (pin "4") (pinfunction "VDD_4") (pintype "bidirectional"))
      (node (ref "U$118") (pin "4") (pinfunction "VDD_4") (pintype "bidirectional"))
      (node (ref "U$119") (pin "4") (pinfunction "VDD_4") (pintype "bidirectional"))
      (node (ref "U$12") (pin "4") (pinfunction "VDD_4") (pintype "bidirectional"))
      (node (ref "U$120") (pin "4") (pinfunction "VDD_4") (pintype "bidirectional"))
      (node (ref "U$121") (pin "4") (pinfunction "VDD_4") (pintype "bidirectional"))
      (node (ref "U$122") (pin "4") (pinfunction "VDD_4") (pintype "bidirectional"))
      (node (ref "U$123") (pin "4") (pinfunction "VDD_4") (pintype "bidirectional"))
      (node (ref "U$124") (pin "4") (pinfunction "VDD_4") (pintype "bidirectional"))
      (node (ref "U$125") (pin "4") (pinfunction "VDD_4") (pintype "bidirectional"))
      (node (ref "U$126") (pin "4") (pinfunction "VDD_4") (pintype "bidirectional"))
      (node (ref "U$127") (pin "4") (pinfunction "VDD_4") (pintype "bidirectional"))
      (node (ref "U$128") (pin "4") (pinfunction "VDD_4") (pintype "bidirectional"))
      (node (ref "U$129") (pin "4") (pinfunction "VDD_4") (pintype "bidirectional"))
      (node (ref "U$13") (pin "4") (pinfunction "VDD_4") (pintype "bidirectional"))
      (node (ref "U$130") (pin "4") (pinfunction "VDD_4") (pintype "bidirectional"))
      (node (ref "U$131") (pin "4") (pinfunction "VDD_4") (pintype "bidirectional"))
      (node (ref "U$132") (pin "4") (pinfunction "VDD_4") (pintype "bidirectional"))
      (node (ref "U$133") (pin "4") (pinfunction "VDD_4") (pintype "bidirectional"))
      (node (ref "U$134") (pin "4") (pinfunction "VDD_4") (pintype "bidirectional"))
      (node (ref "U$135") (pin "4") (pinfunction "VDD_4") (pintype "bidirectional"))
      (node (ref "U$136") (pin "4") (pinfunction "VDD_4") (pintype "bidirectional"))
      (node (ref "U$137") (pin "4") (pinfunction "VDD_4") (pintype "bidirectional"))
      (node (ref "U$138") (pin "4") (pinfunction "VDD_4") (pintype "bidirectional"))
      (node (ref "U$139") (pin "4") (pinfunction "VDD_4") (pintype "bidirectional"))
      (node (ref "U$14") (pin "4") (pinfunction "VDD_4") (pintype "bidirectional"))
      (node (ref "U$140") (pin "4") (pinfunction "VDD_4") (pintype "bidirectional"))
      (node (ref "U$141") (pin "4") (pinfunction "VDD_4") (pintype "bidirectional"))
      (node (ref "U$142") (pin "4") (pinfunction "VDD_4") (pintype "bidirectional"))
      (node (ref "U$143") (pin "4") (pinfunction "VDD_4") (pintype "bidirectional"))
      (node (ref "U$144") (pin "4") (pinfunction "VDD_4") (pintype "bidirectional"))
      (node (ref "U$145") (pin "4") (pinfunction "VDD_4") (pintype "bidirectional"))
      (node (ref "U$146") (pin "4") (pinfunction "VDD_4") (pintype "bidirectional"))
      (node (ref "U$147") (pin "4") (pinfunction "VDD_4") (pintype "bidirectional"))
      (node (ref "U$148") (pin "4") (pinfunction "VDD_4") (pintype "bidirectional"))
      (node (ref "U$149") (pin "4") (pinfunction "VDD_4") (pintype "bidirectional"))
      (node (ref "U$15") (pin "4") (pinfunction "VDD_4") (pintype "bidirectional"))
      (node (ref "U$150") (pin "4") (pinfunction "VDD_4") (pintype "bidirectional"))
      (node (ref "U$151") (pin "4") (pinfunction "VDD_4") (pintype "bidirectional"))
      (node (ref "U$152") (pin "4") (pinfunction "VDD_4") (pintype "bidirectional"))
      (node (ref "U$153") (pin "4") (pinfunction "VDD_4") (pintype "bidirectional"))
      (node (ref "U$154") (pin "4") (pinfunction "VDD_4") (pintype "bidirectional"))
      (node (ref "U$155") (pin "4") (pinfunction "VDD_4") (pintype "bidirectional"))
      (node (ref "U$156") (pin "4") (pinfunction "VDD_4") (pintype "bidirectional"))
      (node (ref "U$157") (pin "4") (pinfunction "VDD_4") (pintype "bidirectional"))
      (node (ref "U$158") (pin "4") (pinfunction "VDD_4") (pintype "bidirectional"))
      (node (ref "U$159") (pin "4") (pinfunction "VDD_4") (pintype "bidirectional"))
      (node (ref "U$16") (pin "4") (pinfunction "VDD_4") (pintype "bidirectional"))
      (node (ref "U$160") (pin "4") (pinfunction "VDD_4") (pintype "bidirectional"))
      (node (ref "U$161") (pin "4") (pinfunction "VDD_4") (pintype "bidirectional"))
      (node (ref "U$162") (pin "4") (pinfunction "VDD_4") (pintype "bidirectional"))
      (node (ref "U$163") (pin "4") (pinfunction "VDD_4") (pintype "bidirectional"))
      (node (ref "U$164") (pin "4") (pinfunction "VDD_4") (pintype "bidirectional"))
      (node (ref "U$165") (pin "4") (pinfunction "VDD_4") (pintype "bidirectional"))
      (node (ref "U$166") (pin "4") (pinfunction "VDD_4") (pintype "bidirectional"))
      (node (ref "U$167") (pin "4") (pinfunction "VDD_4") (pintype "bidirectional"))
      (node (ref "U$168") (pin "4") (pinfunction "VDD_4") (pintype "bidirectional"))
      (node (ref "U$169") (pin "4") (pinfunction "VDD_4") (pintype "bidirectional"))
      (node (ref "U$17") (pin "4") (pinfunction "VDD_4") (pintype "bidirectional"))
      (node (ref "U$170") (pin "4") (pinfunction "VDD_4") (pintype "bidirectional"))
      (node (ref "U$171") (pin "4") (pinfunction "VDD_4") (pintype "bidirectional"))
      (node (ref "U$172") (pin "4") (pinfunction "VDD_4") (pintype "bidirectional"))
      (node (ref "U$173") (pin "4") (pinfunction "VDD_4") (pintype "bidirectional"))
      (node (ref "U$174") (pin "4") (pinfunction "VDD_4") (pintype "bidirectional"))
      (node (ref "U$175") (pin "4") (pinfunction "VDD_4") (pintype "bidirectional"))
      (node (ref "U$176") (pin "4") (pinfunction "VDD_4") (pintype "bidirectional"))
      (node (ref "U$177") (pin "4") (pinfunction "VDD_4") (pintype "bidirectional"))
      (node (ref "U$178") (pin "4") (pinfunction "VDD_4") (pintype "bidirectional"))
      (node (ref "U$179") (pin "4") (pinfunction "VDD_4") (pintype "bidirectional"))
      (node (ref "U$18") (pin "4") (pinfunction "VDD_4") (pintype "bidirectional"))
      (node (ref "U$180") (pin "4") (pinfunction "VDD_4") (pintype "bidirectional"))
      (node (ref "U$181") (pin "4") (pinfunction "VDD_4") (pintype "bidirectional"))
      (node (ref "U$182") (pin "4") (pinfunction "VDD_4") (pintype "bidirectional"))
      (node (ref "U$183") (pin "4") (pinfunction "VDD_4") (pintype "bidirectional"))
      (node (ref "U$184") (pin "4") (pinfunction "VDD_4") (pintype "bidirectional"))
      (node (ref "U$185") (pin "4") (pinfunction "VDD_4") (pintype "bidirectional"))
      (node (ref "U$186") (pin "4") (pinfunction "VDD_4") (pintype "bidirectional"))
      (node (ref "U$187") (pin "4") (pinfunction "VDD_4") (pintype "bidirectional"))
      (node (ref "U$188") (pin "4") (pinfunction "VDD_4") (pintype "bidirectional"))
      (node (ref "U$189") (pin "4") (pinfunction "VDD_4") (pintype "bidirectional"))
      (node (ref "U$19") (pin "4") (pinfunction "VDD_4") (pintype "bidirectional"))
      (node (ref "U$190") (pin "4") (pinfunction "VDD_4") (pintype "bidirectional"))
      (node (ref "U$191") (pin "4") (pinfunction "VDD_4") (pintype "bidirectional"))
      (node (ref "U$192") (pin "4") (pinfunction "VDD_4") (pintype "bidirectional"))
      (node (ref "U$193") (pin "4") (pinfunction "VDD_4") (pintype "bidirectional"))
      (node (ref "U$194") (pin "4") (pinfunction "VDD_4") (pintype "bidirectional"))
      (node (ref "U$195") (pin "4") (pinfunction "VDD_4") (pintype "bidirectional"))
      (node (ref "U$196") (pin "4") (pinfunction "VDD_4") (pintype "bidirectional"))
      (node (ref "U$197") (pin "4") (pinfunction "VDD_4") (pintype "bidirectional"))
      (node (ref "U$198") (pin "4") (pinfunction "VDD_4") (pintype "bidirectional"))
      (node (ref "U$199") (pin "4") (pinfunction "VDD_4") (pintype "bidirectional"))
      (node (ref "U$2") (pin "4") (pinfunction "VDD_4") (pintype "bidirectional"))
      (node (ref "U$20") (pin "4") (pinfunction "VDD_4") (pintype "bidirectional"))
      (node (ref "U$200") (pin "4") (pinfunction "VDD_4") (pintype "bidirectional"))
      (node (ref "U$201") (pin "4") (pinfunction "VDD_4") (pintype "bidirectional"))
      (node (ref "U$202") (pin "4") (pinfunction "VDD_4") (pintype "bidirectional"))
      (node (ref "U$203") (pin "4") (pinfunction "VDD_4") (pintype "bidirectional"))
      (node (ref "U$204") (pin "4") (pinfunction "VDD_4") (pintype "bidirectional"))
      (node (ref "U$205") (pin "4") (pinfunction "VDD_4") (pintype "bidirectional"))
      (node (ref "U$206") (pin "4") (pinfunction "VDD_4") (pintype "bidirectional"))
      (node (ref "U$207") (pin "4") (pinfunction "VDD_4") (pintype "bidirectional"))
      (node (ref "U$208") (pin "4") (pinfunction "VDD_4") (pintype "bidirectional"))
      (node (ref "U$209") (pin "4") (pinfunction "VDD_4") (pintype "bidirectional"))
      (node (ref "U$21") (pin "4") (pinfunction "VDD_4") (pintype "bidirectional"))
      (node (ref "U$210") (pin "4") (pinfunction "VDD_4") (pintype "bidirectional"))
      (node (ref "U$211") (pin "4") (pinfunction "VDD_4") (pintype "bidirectional"))
      (node (ref "U$212") (pin "4") (pinfunction "VDD_4") (pintype "bidirectional"))
      (node (ref "U$213") (pin "4") (pinfunction "VDD_4") (pintype "bidirectional"))
      (node (ref "U$214") (pin "4") (pinfunction "VDD_4") (pintype "bidirectional"))
      (node (ref "U$215") (pin "4") (pinfunction "VDD_4") (pintype "bidirectional"))
      (node (ref "U$216") (pin "4") (pinfunction "VDD_4") (pintype "bidirectional"))
      (node (ref "U$217") (pin "4") (pinfunction "VDD_4") (pintype "bidirectional"))
      (node (ref "U$218") (pin "4") (pinfunction "VDD_4") (pintype "bidirectional"))
      (node (ref "U$219") (pin "4") (pinfunction "VDD_4") (pintype "bidirectional"))
      (node (ref "U$22") (pin "4") (pinfunction "VDD_4") (pintype "bidirectional"))
      (node (ref "U$220") (pin "4") (pinfunction "VDD_4") (pintype "bidirectional"))
      (node (ref "U$221") (pin "4") (pinfunction "VDD_4") (pintype "bidirectional"))
      (node (ref "U$222") (pin "4") (pinfunction "VDD_4") (pintype "bidirectional"))
      (node (ref "U$223") (pin "4") (pinfunction "VDD_4") (pintype "bidirectional"))
      (node (ref "U$224") (pin "4") (pinfunction "VDD_4") (pintype "bidirectional"))
      (node (ref "U$225") (pin "4") (pinfunction "VDD_4") (pintype "bidirectional"))
      (node (ref "U$226") (pin "4") (pinfunction "VDD_4") (pintype "bidirectional"))
      (node (ref "U$227") (pin "4") (pinfunction "VDD_4") (pintype "bidirectional"))
      (node (ref "U$228") (pin "4") (pinfunction "VDD_4") (pintype "bidirectional"))
      (node (ref "U$229") (pin "4") (pinfunction "VDD_4") (pintype "bidirectional"))
      (node (ref "U$23") (pin "4") (pinfunction "VDD_4") (pintype "bidirectional"))
      (node (ref "U$230") (pin "4") (pinfunction "VDD_4") (pintype "bidirectional"))
      (node (ref "U$231") (pin "4") (pinfunction "VDD_4") (pintype "bidirectional"))
      (node (ref "U$232") (pin "4") (pinfunction "VDD_4") (pintype "bidirectional"))
      (node (ref "U$233") (pin "4") (pinfunction "VDD_4") (pintype "bidirectional"))
      (node (ref "U$234") (pin "4") (pinfunction "VDD_4") (pintype "bidirectional"))
      (node (ref "U$235") (pin "4") (pinfunction "VDD_4") (pintype "bidirectional"))
      (node (ref "U$236") (pin "4") (pinfunction "VDD_4") (pintype "bidirectional"))
      (node (ref "U$237") (pin "4") (pinfunction "VDD_4") (pintype "bidirectional"))
      (node (ref "U$238") (pin "4") (pinfunction "VDD_4") (pintype "bidirectional"))
      (node (ref "U$239") (pin "4") (pinfunction "VDD_4") (pintype "bidirectional"))
      (node (ref "U$24") (pin "4") (pinfunction "VDD_4") (pintype "bidirectional"))
      (node (ref "U$240") (pin "4") (pinfunction "VDD_4") (pintype "bidirectional"))
      (node (ref "U$241") (pin "4") (pinfunction "VDD_4") (pintype "bidirectional"))
      (node (ref "U$242") (pin "4") (pinfunction "VDD_4") (pintype "bidirectional"))
      (node (ref "U$243") (pin "4") (pinfunction "VDD_4") (pintype "bidirectional"))
      (node (ref "U$244") (pin "4") (pinfunction "VDD_4") (pintype "bidirectional"))
      (node (ref "U$245") (pin "4") (pinfunction "VDD_4") (pintype "bidirectional"))
      (node (ref "U$246") (pin "4") (pinfunction "VDD_4") (pintype "bidirectional"))
      (node (ref "U$247") (pin "4") (pinfunction "VDD_4") (pintype "bidirectional"))
      (node (ref "U$248") (pin "4") (pinfunction "VDD_4") (pintype "bidirectional"))
      (node (ref "U$249") (pin "4") (pinfunction "VDD_4") (pintype "bidirectional"))
      (node (ref "U$25") (pin "4") (pinfunction "VDD_4") (pintype "bidirectional"))
      (node (ref "U$250") (pin "4") (pinfunction "VDD_4") (pintype "bidirectional"))
      (node (ref "U$251") (pin "4") (pinfunction "VDD_4") (pintype "bidirectional"))
      (node (ref "U$252") (pin "4") (pinfunction "VDD_4") (pintype "bidirectional"))
      (node (ref "U$253") (pin "4") (pinfunction "VDD_4") (pintype "bidirectional"))
      (node (ref "U$254") (pin "4") (pinfunction "VDD_4") (pintype "bidirectional"))
      (node (ref "U$255") (pin "4") (pinfunction "VDD_4") (pintype "bidirectional"))
      (node (ref "U$256") (pin "4") (pinfunction "VDD_4") (pintype "bidirectional"))
      (node (ref "U$26") (pin "4") (pinfunction "VDD_4") (pintype "bidirectional"))
      (node (ref "U$27") (pin "4") (pinfunction "VDD_4") (pintype "bidirectional"))
      (node (ref "U$28") (pin "4") (pinfunction "VDD_4") (pintype "bidirectional"))
      (node (ref "U$29") (pin "4") (pinfunction "VDD_4") (pintype "bidirectional"))
      (node (ref "U$3") (pin "4") (pinfunction "VDD_4") (pintype "bidirectional"))
      (node (ref "U$30") (pin "4") (pinfunction "VDD_4") (pintype "bidirectional"))
      (node (ref "U$31") (pin "4") (pinfunction "VDD_4") (pintype "bidirectional"))
      (node (ref "U$32") (pin "4") (pinfunction "VDD_4") (pintype "bidirectional"))
      (node (ref "U$33") (pin "4") (pinfunction "VDD_4") (pintype "bidirectional"))
      (node (ref "U$34") (pin "4") (pinfunction "VDD_4") (pintype "bidirectional"))
      (node (ref "U$35") (pin "4") (pinfunction "VDD_4") (pintype "bidirectional"))
      (node (ref "U$36") (pin "4") (pinfunction "VDD_4") (pintype "bidirectional"))
      (node (ref "U$37") (pin "4") (pinfunction "VDD_4") (pintype "bidirectional"))
      (node (ref "U$38") (pin "4") (pinfunction "VDD_4") (pintype "bidirectional"))
      (node (ref "U$39") (pin "4") (pinfunction "VDD_4") (pintype "bidirectional"))
      (node (ref "U$4") (pin "4") (pinfunction "VDD_4") (pintype "bidirectional"))
      (node (ref "U$40") (pin "4") (pinfunction "VDD_4") (pintype "bidirectional"))
      (node (ref "U$41") (pin "4") (pinfunction "VDD_4") (pintype "bidirectional"))
      (node (ref "U$42") (pin "4") (pinfunction "VDD_4") (pintype "bidirectional"))
      (node (ref "U$43") (pin "4") (pinfunction "VDD_4") (pintype "bidirectional"))
      (node (ref "U$44") (pin "4") (pinfunction "VDD_4") (pintype "bidirectional"))
      (node (ref "U$45") (pin "4") (pinfunction "VDD_4") (pintype "bidirectional"))
      (node (ref "U$46") (pin "4") (pinfunction "VDD_4") (pintype "bidirectional"))
      (node (ref "U$47") (pin "4") (pinfunction "VDD_4") (pintype "bidirectional"))
      (node (ref "U$48") (pin "4") (pinfunction "VDD_4") (pintype "bidirectional"))
      (node (ref "U$49") (pin "4") (pinfunction "VDD_4") (pintype "bidirectional"))
      (node (ref "U$5") (pin "4") (pinfunction "VDD_4") (pintype "bidirectional"))
      (node (ref "U$50") (pin "4") (pinfunction "VDD_4") (pintype "bidirectional"))
      (node (ref "U$51") (pin "4") (pinfunction "VDD_4") (pintype "bidirectional"))
      (node (ref "U$52") (pin "4") (pinfunction "VDD_4") (pintype "bidirectional"))
      (node (ref "U$53") (pin "4") (pinfunction "VDD_4") (pintype "bidirectional"))
      (node (ref "U$54") (pin "4") (pinfunction "VDD_4") (pintype "bidirectional"))
      (node (ref "U$55") (pin "4") (pinfunction "VDD_4") (pintype "bidirectional"))
      (node (ref "U$56") (pin "4") (pinfunction "VDD_4") (pintype "bidirectional"))
      (node (ref "U$57") (pin "4") (pinfunction "VDD_4") (pintype "bidirectional"))
      (node (ref "U$58") (pin "4") (pinfunction "VDD_4") (pintype "bidirectional"))
      (node (ref "U$59") (pin "4") (pinfunction "VDD_4") (pintype "bidirectional"))
      (node (ref "U$6") (pin "4") (pinfunction "VDD_4") (pintype "bidirectional"))
      (node (ref "U$60") (pin "4") (pinfunction "VDD_4") (pintype "bidirectional"))
      (node (ref "U$61") (pin "4") (pinfunction "VDD_4") (pintype "bidirectional"))
      (node (ref "U$62") (pin "4") (pinfunction "VDD_4") (pintype "bidirectional"))
      (node (ref "U$63") (pin "4") (pinfunction "VDD_4") (pintype "bidirectional"))
      (node (ref "U$64") (pin "4") (pinfunction "VDD_4") (pintype "bidirectional"))
      (node (ref "U$65") (pin "4") (pinfunction "VDD_4") (pintype "bidirectional"))
      (node (ref "U$66") (pin "4") (pinfunction "VDD_4") (pintype "bidirectional"))
      (node (ref "U$67") (pin "4") (pinfunction "VDD_4") (pintype "bidirectional"))
      (node (ref "U$68") (pin "4") (pinfunction "VDD_4") (pintype "bidirectional"))
      (node (ref "U$69") (pin "4") (pinfunction "VDD_4") (pintype "bidirectional"))
      (node (ref "U$7") (pin "4") (pinfunction "VDD_4") (pintype "bidirectional"))
      (node (ref "U$70") (pin "4") (pinfunction "VDD_4") (pintype "bidirectional"))
      (node (ref "U$71") (pin "4") (pinfunction "VDD_4") (pintype "bidirectional"))
      (node (ref "U$72") (pin "4") (pinfunction "VDD_4") (pintype "bidirectional"))
      (node (ref "U$73") (pin "4") (pinfunction "VDD_4") (pintype "bidirectional"))
      (node (ref "U$74") (pin "4") (pinfunction "VDD_4") (pintype "bidirectional"))
      (node (ref "U$75") (pin "4") (pinfunction "VDD_4") (pintype "bidirectional"))
      (node (ref "U$76") (pin "4") (pinfunction "VDD_4") (pintype "bidirectional"))
      (node (ref "U$77") (pin "4") (pinfunction "VDD_4") (pintype "bidirectional"))
      (node (ref "U$78") (pin "4") (pinfunction "VDD_4") (pintype "bidirectional"))
      (node (ref "U$79") (pin "4") (pinfunction "VDD_4") (pintype "bidirectional"))
      (node (ref "U$8") (pin "4") (pinfunction "VDD_4") (pintype "bidirectional"))
      (node (ref "U$80") (pin "4") (pinfunction "VDD_4") (pintype "bidirectional"))
      (node (ref "U$81") (pin "4") (pinfunction "VDD_4") (pintype "bidirectional"))
      (node (ref "U$82") (pin "4") (pinfunction "VDD_4") (pintype "bidirectional"))
      (node (ref "U$83") (pin "4") (pinfunction "VDD_4") (pintype "bidirectional"))
      (node (ref "U$84") (pin "4") (pinfunction "VDD_4") (pintype "bidirectional"))
      (node (ref "U$85") (pin "4") (pinfunction "VDD_4") (pintype "bidirectional"))
      (node (ref "U$86") (pin "4") (pinfunction "VDD_4") (pintype "bidirectional"))
      (node (ref "U$87") (pin "4") (pinfunction "VDD_4") (pintype "bidirectional"))
      (node (ref "U$88") (pin "4") (pinfunction "VDD_4") (pintype "bidirectional"))
      (node (ref "U$89") (pin "4") (pinfunction "VDD_4") (pintype "bidirectional"))
      (node (ref "U$9") (pin "4") (pinfunction "VDD_4") (pintype "bidirectional"))
      (node (ref "U$90") (pin "4") (pinfunction "VDD_4") (pintype "bidirectional"))
      (node (ref "U$91") (pin "4") (pinfunction "VDD_4") (pintype "bidirectional"))
      (node (ref "U$92") (pin "4") (pinfunction "VDD_4") (pintype "bidirectional"))
      (node (ref "U$93") (pin "4") (pinfunction "VDD_4") (pintype "bidirectional"))
      (node (ref "U$94") (pin "4") (pinfunction "VDD_4") (pintype "bidirectional"))
      (node (ref "U$95") (pin "4") (pinfunction "VDD_4") (pintype "bidirectional"))
      (node (ref "U$96") (pin "4") (pinfunction "VDD_4") (pintype "bidirectional"))
      (node (ref "U$97") (pin "4") (pinfunction "VDD_4") (pintype "bidirectional"))
      (node (ref "U$98") (pin "4") (pinfunction "VDD_4") (pintype "bidirectional"))
      (node (ref "U$99") (pin "4") (pinfunction "VDD_4") (pintype "bidirectional"))
    )
  )
)
